# DatatrakEPROMEmu.net
KiCad netlist of a schematic drawn in EAGLE
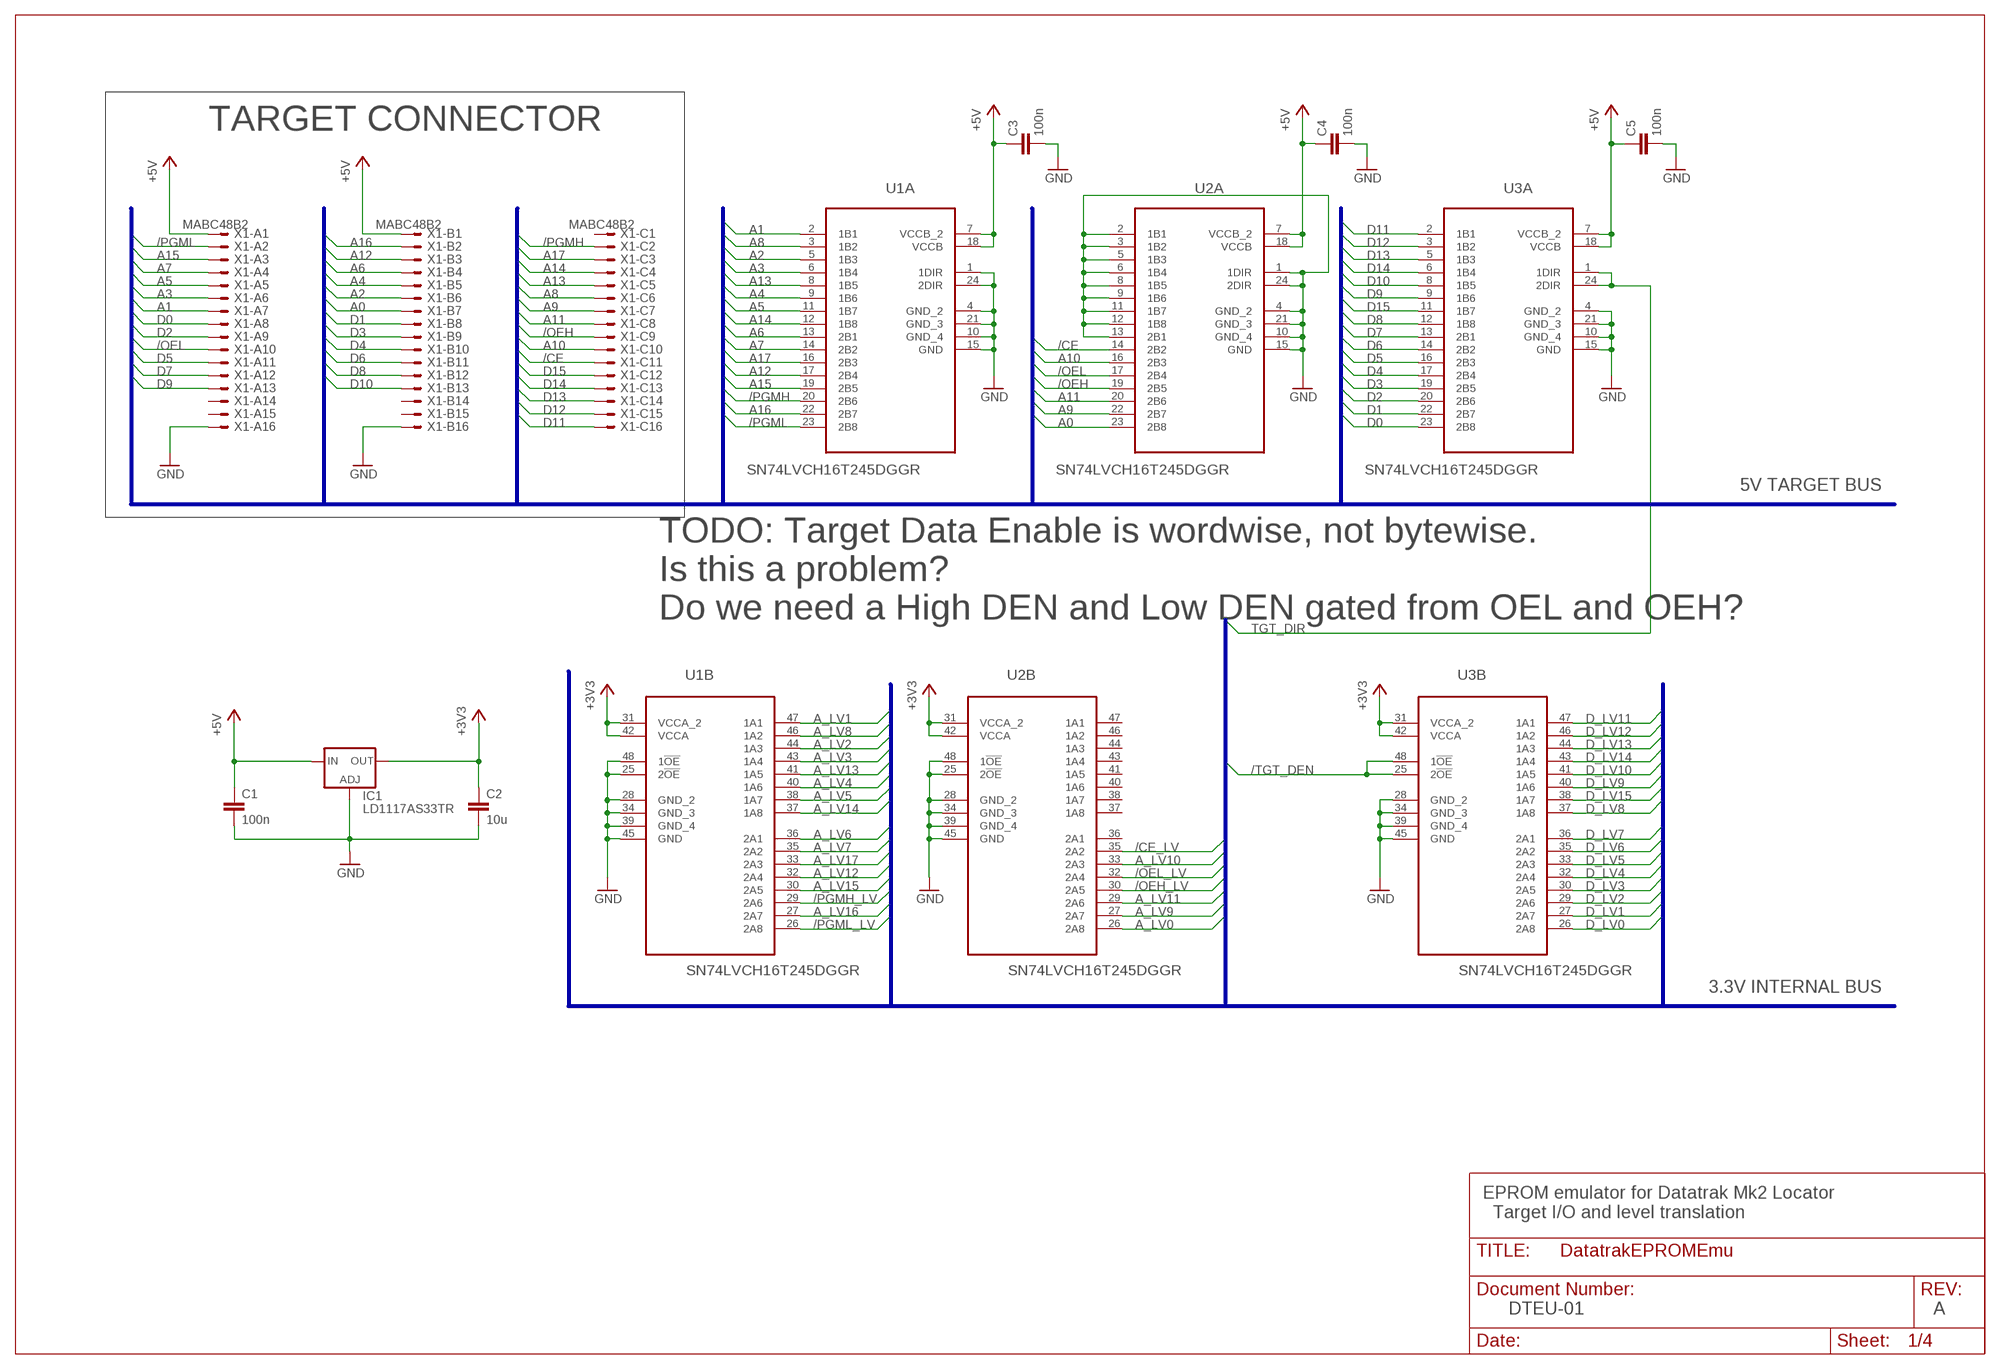
[diagram p0: schematic, sheet 1]
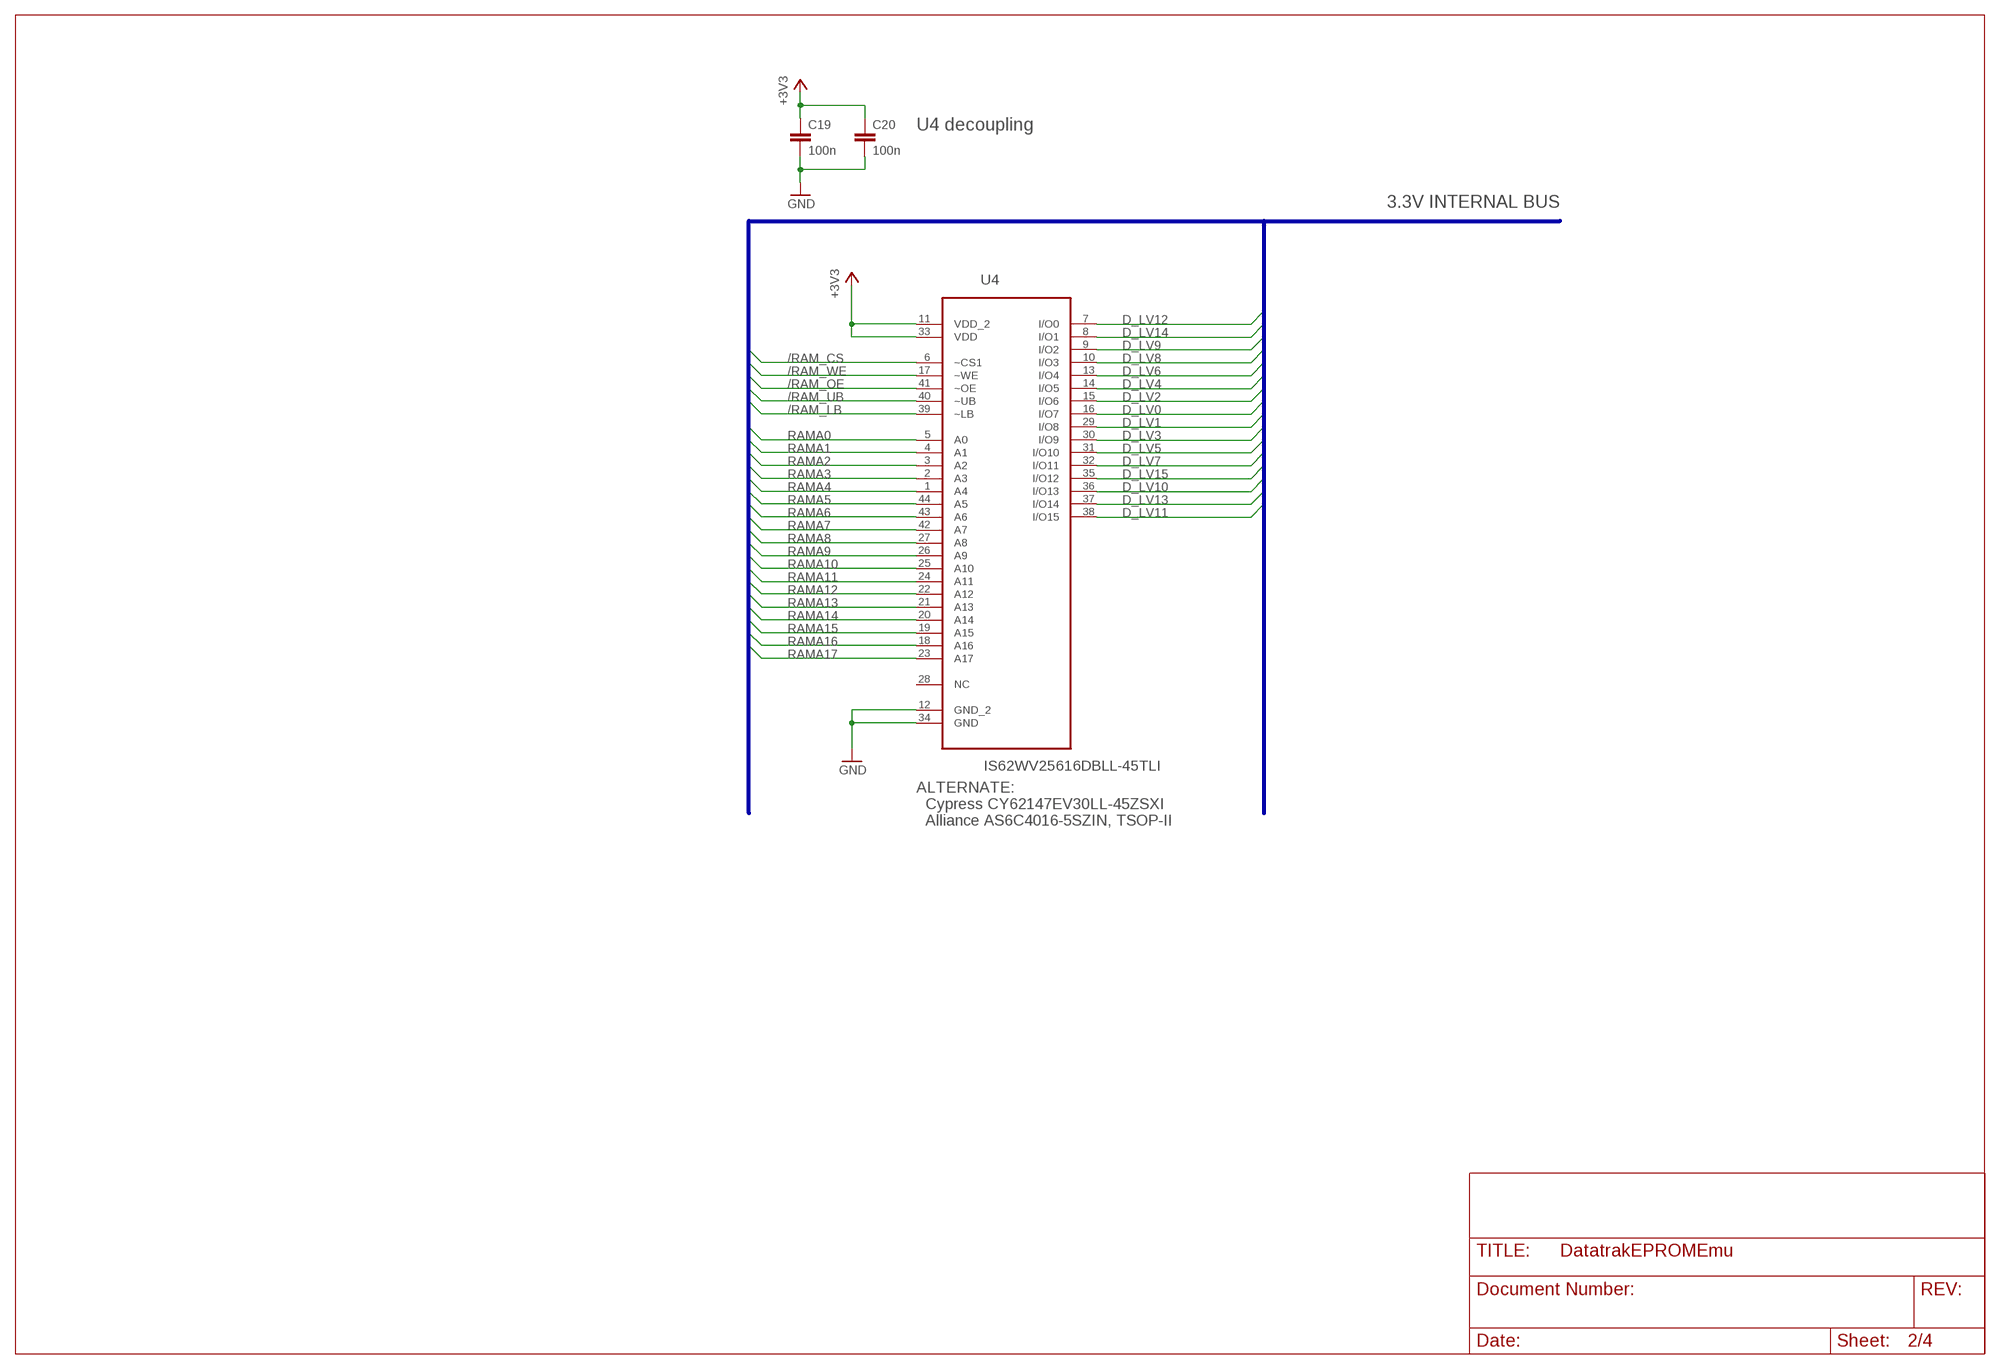
[diagram p1: schematic, sheet 2]
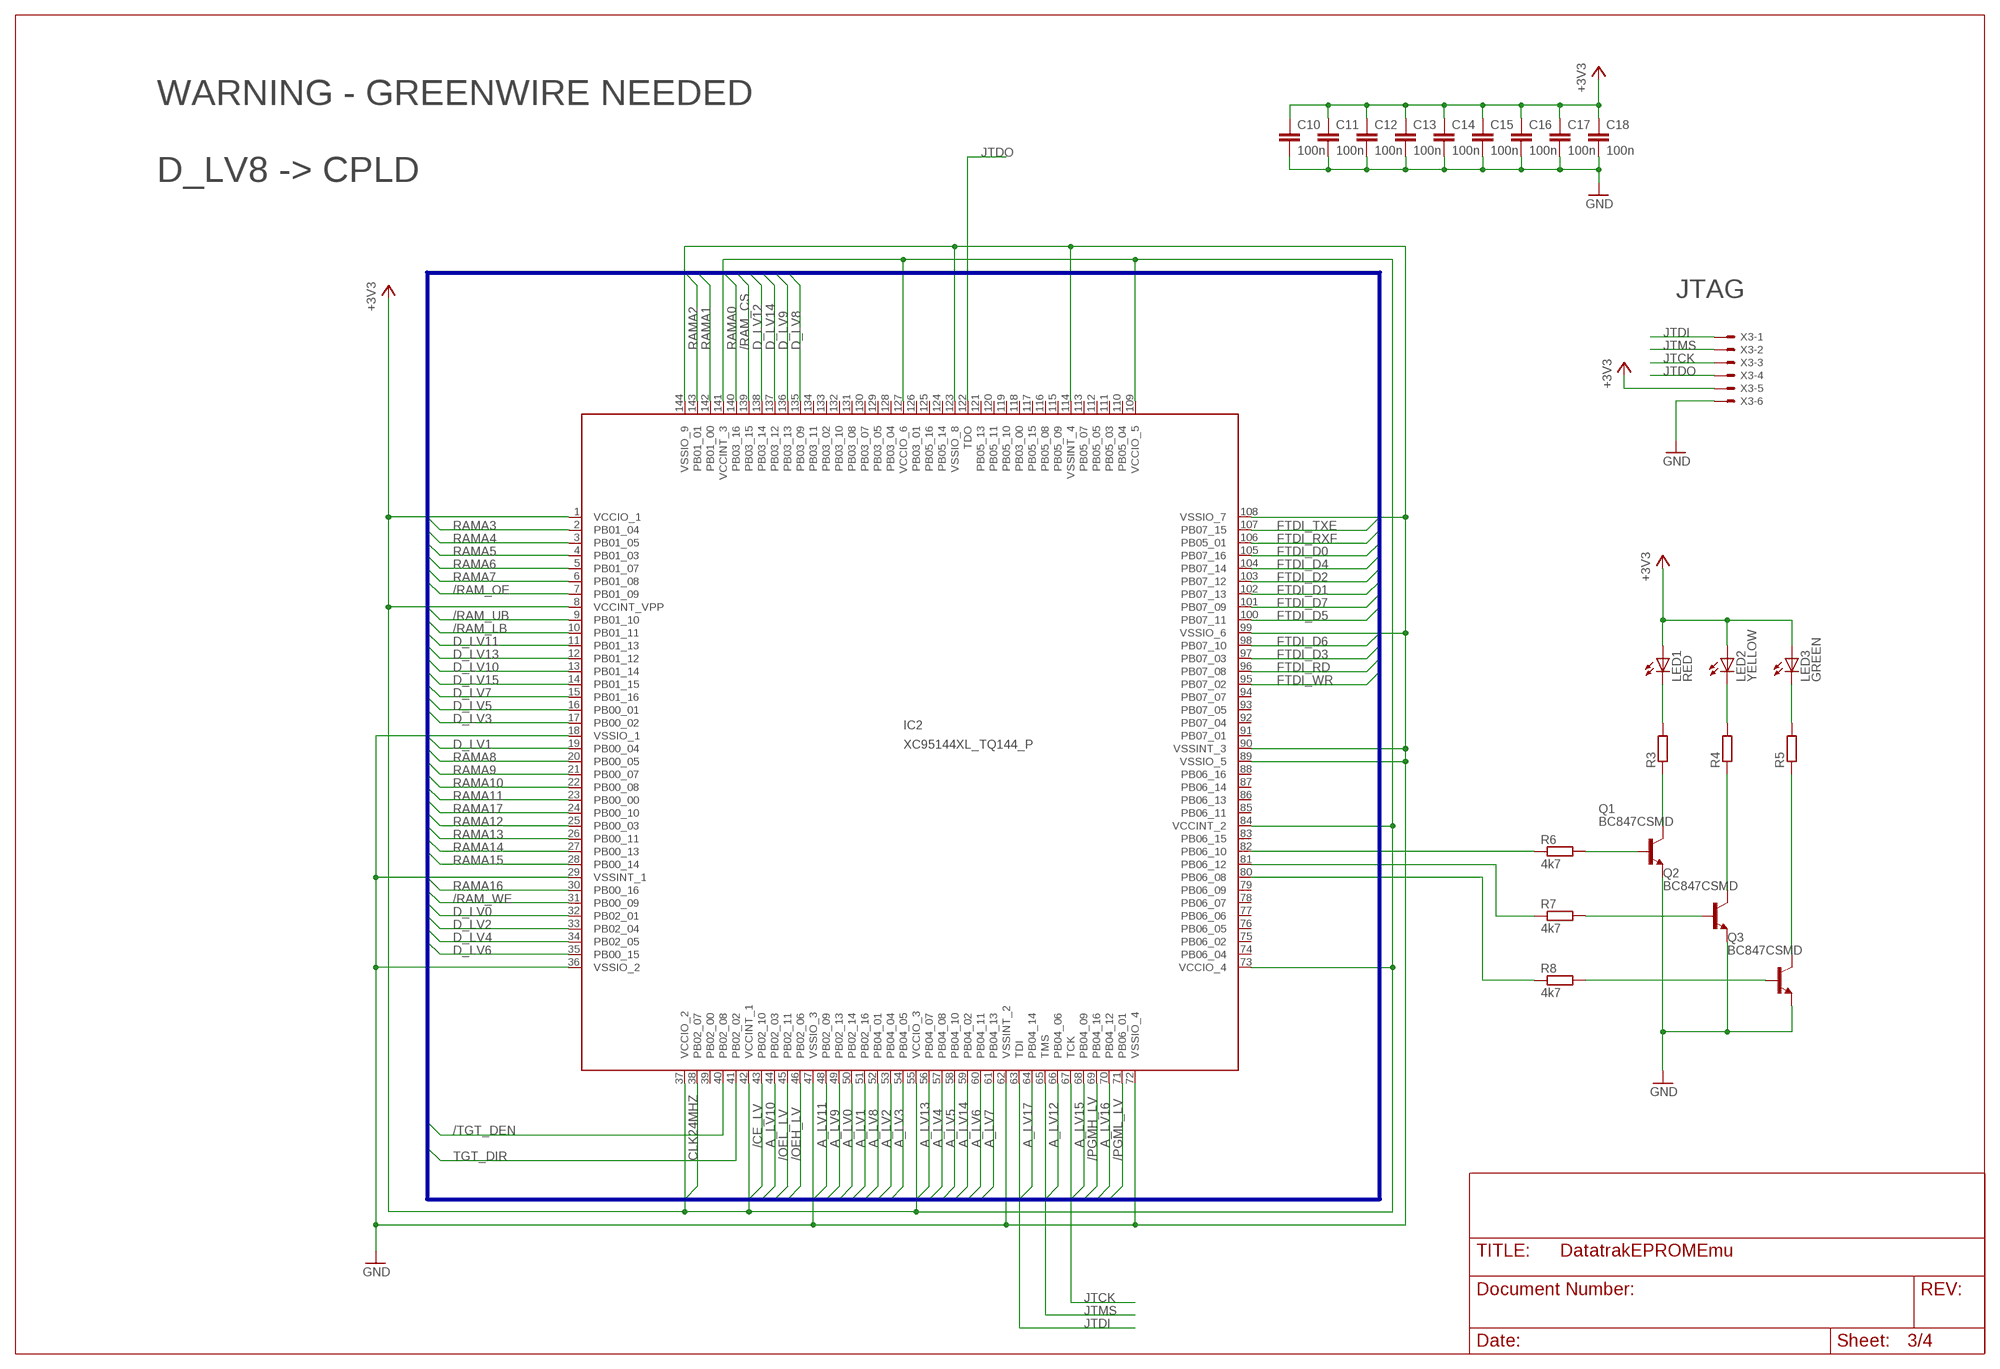
[diagram p2: schematic, sheet 3]
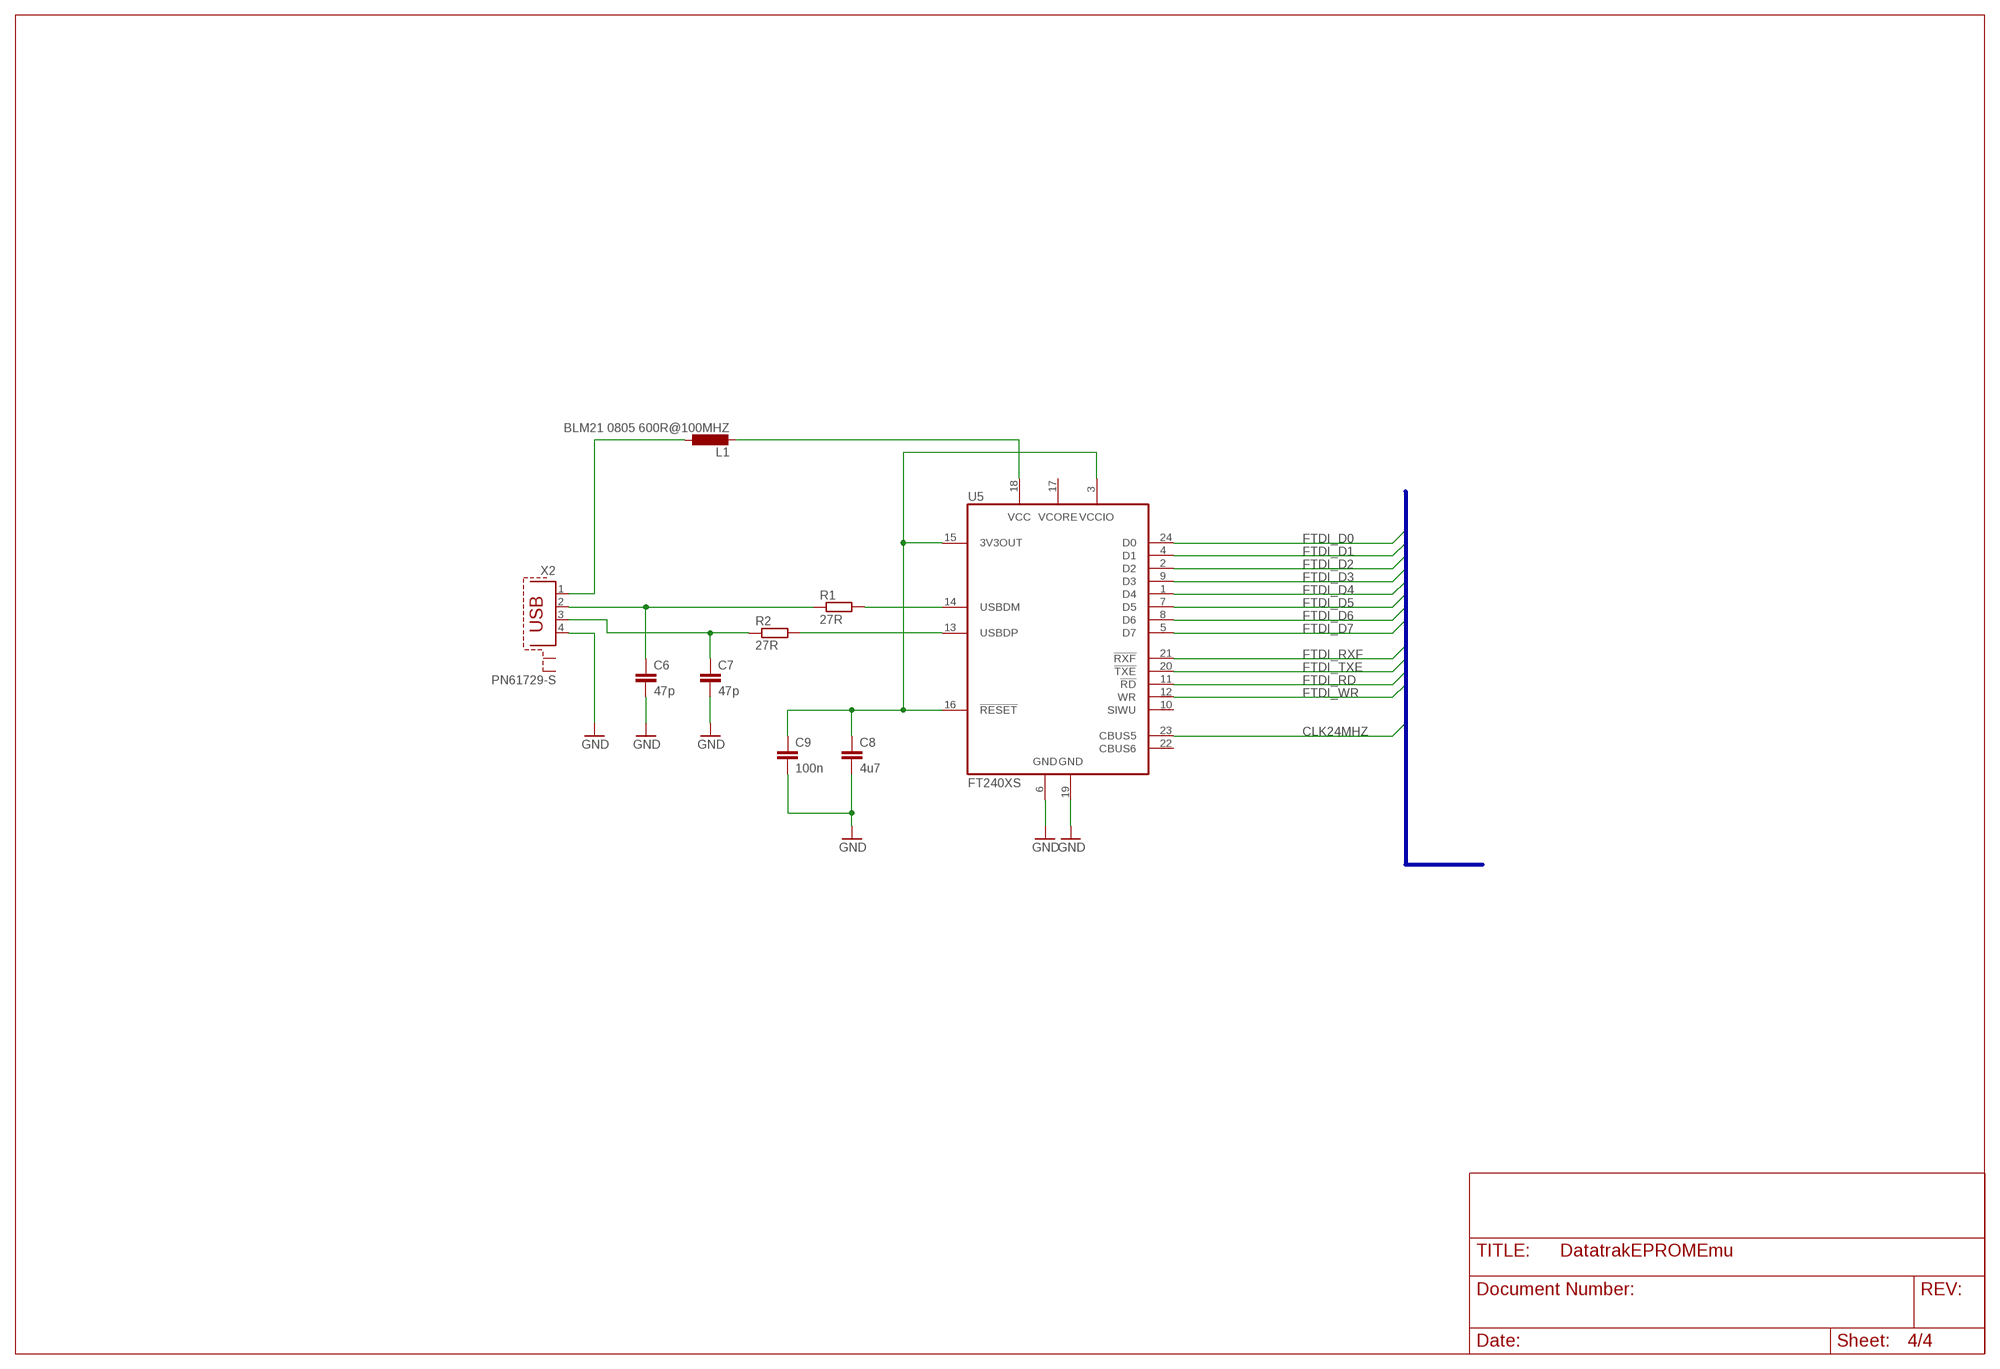
[diagram p3: schematic, sheet 4]

(export (version "E")
  (design (tool "Eeschema 10.0.6"))
  (components
    (comp (ref "C19")
      (value "100n")
      (footprint "eagle-import:C0805")
      (libsource (lib "eagle-import") (part "C-EUC0805"))
    )
    (comp (ref "C20")
      (value "100n")
      (footprint "eagle-import:C0805")
      (libsource (lib "eagle-import") (part "C-EUC0805"))
    )
    (comp (ref "U4")
      (value "IS62WV25616DBLL-45TLI")
      (footprint "eagle-import:SOP80P1176X120-44N")
      (libsource (lib "eagle-import") (part "IS62WV25616DBLL-45TLI"))
    )
    (comp (ref "C1")
      (value "100n")
      (footprint "eagle-import:C0805")
      (libsource (lib "eagle-import") (part "C-EUC0805"))
    )
    (comp (ref "C2")
      (value "10u")
      (footprint "eagle-import:C0805")
      (libsource (lib "eagle-import") (part "C-EUC0805"))
    )
    (comp (ref "C3")
      (value "100n")
      (footprint "eagle-import:C0805")
      (libsource (lib "eagle-import") (part "C-EUC0805"))
    )
    (comp (ref "C4")
      (value "100n")
      (footprint "eagle-import:C0805")
      (libsource (lib "eagle-import") (part "C-EUC0805"))
    )
    (comp (ref "C5")
      (value "100n")
      (footprint "eagle-import:C0805")
      (libsource (lib "eagle-import") (part "C-EUC0805"))
    )
    (comp (ref "IC1")
      (value "LD1117AS33TR")
      (footprint "eagle-import:SOT223")
      (libsource (lib "eagle-import") (part "LD117A?S33TR"))
    )
    (comp (ref "U1")
      (value "SN74LVCH16T245DGGR")
      (footprint "eagle-import:SOP50P810X120-48N")
      (libsource (lib "eagle-import") (part "SN74LVCH16T245DGGR"))
    )
    (comp (ref "U2")
      (value "SN74LVCH16T245DGGR")
      (footprint "eagle-import:SOP50P810X120-48N")
      (libsource (lib "eagle-import") (part "SN74LVCH16T245DGGR"))
    )
    (comp (ref "U3")
      (value "SN74LVCH16T245DGGR")
      (footprint "eagle-import:SOP50P810X120-48N")
      (libsource (lib "eagle-import") (part "SN74LVCH16T245DGGR"))
    )
    (comp (ref "X1")
      (value "MABC48B2")
      (footprint "eagle-import:MABC48B2")
      (libsource (lib "eagle-import") (part "MABC48B2"))
    )
    (comp (ref "C6")
      (value "47p")
      (footprint "eagle-import:C0805")
      (libsource (lib "eagle-import") (part "C-EUC0805"))
    )
    (comp (ref "C7")
      (value "47p")
      (footprint "eagle-import:C0805")
      (libsource (lib "eagle-import") (part "C-EUC0805"))
    )
    (comp (ref "C8")
      (value "4u7")
      (footprint "eagle-import:C0805")
      (libsource (lib "eagle-import") (part "C-EUC0805"))
    )
    (comp (ref "C9")
      (value "100n")
      (footprint "eagle-import:C0805")
      (libsource (lib "eagle-import") (part "C-EUC0805"))
    )
    (comp (ref "L1")
      (value "BLM21 0805 600R@100MHZ")
      (footprint "eagle-import:L2012C")
      (libsource (lib "eagle-import") (part "L-EUL2012C"))
    )
    (comp (ref "R1")
      (value "27R")
      (footprint "eagle-import:R0805")
      (libsource (lib "eagle-import") (part "R-EU_R0805"))
    )
    (comp (ref "R2")
      (value "27R")
      (footprint "eagle-import:R0805")
      (libsource (lib "eagle-import") (part "R-EU_R0805"))
    )
    (comp (ref "U5")
      (value "FT240XS")
      (footprint "eagle-import:SSOP24")
      (libsource (lib "eagle-import") (part "FT240XS"))
    )
    (comp (ref "X2")
      (value "PN61729-S")
      (footprint "eagle-import:PN61729-S")
      (libsource (lib "eagle-import") (part "PN61729-S"))
    )
    (comp (ref "C10")
      (value "100n")
      (footprint "eagle-import:C0805")
      (libsource (lib "eagle-import") (part "C-EUC0805"))
    )
    (comp (ref "C11")
      (value "100n")
      (footprint "eagle-import:C0805")
      (libsource (lib "eagle-import") (part "C-EUC0805"))
    )
    (comp (ref "C12")
      (value "100n")
      (footprint "eagle-import:C0805")
      (libsource (lib "eagle-import") (part "C-EUC0805"))
    )
    (comp (ref "C13")
      (value "100n")
      (footprint "eagle-import:C0805")
      (libsource (lib "eagle-import") (part "C-EUC0805"))
    )
    (comp (ref "C14")
      (value "100n")
      (footprint "eagle-import:C0805")
      (libsource (lib "eagle-import") (part "C-EUC0805"))
    )
    (comp (ref "C15")
      (value "100n")
      (footprint "eagle-import:C0805")
      (libsource (lib "eagle-import") (part "C-EUC0805"))
    )
    (comp (ref "C16")
      (value "100n")
      (footprint "eagle-import:C0805")
      (libsource (lib "eagle-import") (part "C-EUC0805"))
    )
    (comp (ref "C17")
      (value "100n")
      (footprint "eagle-import:C0805")
      (libsource (lib "eagle-import") (part "C-EUC0805"))
    )
    (comp (ref "C18")
      (value "100n")
      (footprint "eagle-import:C0805")
      (libsource (lib "eagle-import") (part "C-EUC0805"))
    )
    (comp (ref "IC2")
      (value "XC95144XL_TQ144_P")
      (footprint "eagle-import:TQ144")
      (libsource (lib "eagle-import") (part "XC95144XL_TQ144_P"))
    )
    (comp (ref "LED1")
      (value "RED")
      (footprint "eagle-import:SML0805")
      (libsource (lib "eagle-import") (part "LEDSML0805"))
    )
    (comp (ref "LED2")
      (value "YELLOW")
      (footprint "eagle-import:SML0805")
      (libsource (lib "eagle-import") (part "LEDSML0805"))
    )
    (comp (ref "LED3")
      (value "GREEN")
      (footprint "eagle-import:SML0805")
      (libsource (lib "eagle-import") (part "LEDSML0805"))
    )
    (comp (ref "Q1")
      (value "BC847CSMD")
      (footprint "eagle-import:SOT23")
      (libsource (lib "eagle-import") (part "BC847SMDC"))
    )
    (comp (ref "Q2")
      (value "BC847CSMD")
      (footprint "eagle-import:SOT23")
      (libsource (lib "eagle-import") (part "BC847SMDC"))
    )
    (comp (ref "Q3")
      (value "BC847CSMD")
      (footprint "eagle-import:SOT23")
      (libsource (lib "eagle-import") (part "BC847SMDC"))
    )
    (comp (ref "R3")
      (value "R-EU_R0805")
      (footprint "eagle-import:R0805")
      (libsource (lib "eagle-import") (part "R-EU_R0805"))
    )
    (comp (ref "R4")
      (value "R-EU_R0805")
      (footprint "eagle-import:R0805")
      (libsource (lib "eagle-import") (part "R-EU_R0805"))
    )
    (comp (ref "R5")
      (value "R-EU_R0805")
      (footprint "eagle-import:R0805")
      (libsource (lib "eagle-import") (part "R-EU_R0805"))
    )
    (comp (ref "R6")
      (value "4k7")
      (footprint "eagle-import:R0805")
      (libsource (lib "eagle-import") (part "R-EU_R0805"))
    )
    (comp (ref "R7")
      (value "4k7")
      (footprint "eagle-import:R0805")
      (libsource (lib "eagle-import") (part "R-EU_R0805"))
    )
    (comp (ref "R8")
      (value "4k7")
      (footprint "eagle-import:R0805")
      (libsource (lib "eagle-import") (part "R-EU_R0805"))
    )
    (comp (ref "X3")
      (value "22-23-2061")
      (footprint "eagle-import:22-23-2061")
      (fields (field (name "MF") "MOLEX"))
      (libsource (lib "eagle-import") (part "22-23-2061"))
    )
  )
  (nets
    (net (code "1") (name "+3V3") (class "Default")
      (node (ref "C10") (pin "1") (pinfunction "1_1") (pintype "passive"))
      (node (ref "C11") (pin "1") (pinfunction "1_1") (pintype "passive"))
      (node (ref "C12") (pin "1") (pinfunction "1_1") (pintype "passive"))
      (node (ref "C13") (pin "1") (pinfunction "1_1") (pintype "passive"))
      (node (ref "C14") (pin "1") (pinfunction "1_1") (pintype "passive"))
      (node (ref "C15") (pin "1") (pinfunction "1_1") (pintype "passive"))
      (node (ref "C16") (pin "1") (pinfunction "1_1") (pintype "passive"))
      (node (ref "C17") (pin "1") (pinfunction "1_1") (pintype "passive"))
      (node (ref "C18") (pin "1") (pinfunction "1_1") (pintype "passive"))
      (node (ref "C19") (pin "1") (pinfunction "1_1") (pintype "passive"))
      (node (ref "C2") (pin "1") (pinfunction "1_1") (pintype "passive"))
      (node (ref "C20") (pin "1") (pinfunction "1_1") (pintype "passive"))
      (node (ref "IC1") (pin "4") (pinfunction "OUT_4") (pintype "passive"))
      (node (ref "IC2") (pin "1") (pinfunction "VCCIO_1_1") (pintype "passive"))
      (node (ref "IC2") (pin "109") (pinfunction "VCCIO_5_109") (pintype "passive"))
      (node (ref "IC2") (pin "127") (pinfunction "VCCIO_6_127") (pintype "passive"))
      (node (ref "IC2") (pin "141") (pinfunction "VCCINT_3_141") (pintype "passive"))
      (node (ref "IC2") (pin "37") (pinfunction "VCCIO_2_37") (pintype "passive"))
      (node (ref "IC2") (pin "42") (pinfunction "VCCINT_1_42") (pintype "passive"))
      (node (ref "IC2") (pin "55") (pinfunction "VCCIO_3_55") (pintype "passive"))
      (node (ref "IC2") (pin "73") (pinfunction "VCCIO_4_73") (pintype "passive"))
      (node (ref "IC2") (pin "8") (pinfunction "VCCINT_VPP_8") (pintype "passive"))
      (node (ref "IC2") (pin "84") (pinfunction "VCCINT_2_84") (pintype "passive"))
      (node (ref "LED1") (pin "A") (pinfunction "A_A") (pintype "passive"))
      (node (ref "LED2") (pin "A") (pinfunction "A_A") (pintype "passive"))
      (node (ref "LED3") (pin "A") (pinfunction "A_A") (pintype "passive"))
      (node (ref "U1") (pin "31") (pinfunction "VCCA_2_31") (pintype "power_in"))
      (node (ref "U1") (pin "42") (pinfunction "VCCA_42") (pintype "power_in"))
      (node (ref "U2") (pin "31") (pinfunction "VCCA_2_31") (pintype "power_in"))
      (node (ref "U2") (pin "42") (pinfunction "VCCA_42") (pintype "power_in"))
      (node (ref "U3") (pin "31") (pinfunction "VCCA_2_31") (pintype "power_in"))
      (node (ref "U3") (pin "42") (pinfunction "VCCA_42") (pintype "power_in"))
      (node (ref "U4") (pin "11") (pinfunction "VDD_2_11") (pintype "power_in"))
      (node (ref "U4") (pin "33") (pinfunction "VDD_33") (pintype "power_in"))
      (node (ref "X3") (pin "5") (pinfunction "S_5") (pintype "passive"))
    )
    (net (code "2") (name "+5V") (class "Default")
      (node (ref "C1") (pin "1") (pinfunction "1_1") (pintype "passive"))
      (node (ref "C3") (pin "1") (pinfunction "1_1") (pintype "passive"))
      (node (ref "C4") (pin "1") (pinfunction "1_1") (pintype "passive"))
      (node (ref "C5") (pin "1") (pinfunction "1_1") (pintype "passive"))
      (node (ref "IC1") (pin "3") (pinfunction "IN_3") (pintype "input"))
      (node (ref "U1") (pin "18") (pinfunction "VCCB_18") (pintype "power_in"))
      (node (ref "U1") (pin "7") (pinfunction "VCCB_2_7") (pintype "power_in"))
      (node (ref "U2") (pin "18") (pinfunction "VCCB_18") (pintype "power_in"))
      (node (ref "U2") (pin "7") (pinfunction "VCCB_2_7") (pintype "power_in"))
      (node (ref "U3") (pin "18") (pinfunction "VCCB_18") (pintype "power_in"))
      (node (ref "U3") (pin "7") (pinfunction "VCCB_2_7") (pintype "power_in"))
      (node (ref "X1") (pin "A1") (pinfunction "S_A1") (pintype "passive"))
      (node (ref "X1") (pin "B1") (pinfunction "S_B1") (pintype "passive"))
    )
    (net (code "3") (name "A0") (class "Default")
      (node (ref "U2") (pin "23") (pinfunction "2B8_23") (pintype "output"))
      (node (ref "X1") (pin "B7") (pinfunction "S_B7") (pintype "passive"))
    )
    (net (code "4") (name "A1") (class "Default")
      (node (ref "U1") (pin "2") (pinfunction "1B1_2") (pintype "output"))
      (node (ref "X1") (pin "A7") (pinfunction "S_A7") (pintype "passive"))
    )
    (net (code "5") (name "A2") (class "Default")
      (node (ref "U1") (pin "5") (pinfunction "1B3_5") (pintype "output"))
      (node (ref "X1") (pin "B6") (pinfunction "S_B6") (pintype "passive"))
    )
    (net (code "6") (name "A3") (class "Default")
      (node (ref "U1") (pin "6") (pinfunction "1B4_6") (pintype "output"))
      (node (ref "X1") (pin "A6") (pinfunction "S_A6") (pintype "passive"))
    )
    (net (code "7") (name "A4") (class "Default")
      (node (ref "U1") (pin "9") (pinfunction "1B6_9") (pintype "output"))
      (node (ref "X1") (pin "B5") (pinfunction "S_B5") (pintype "passive"))
    )
    (net (code "8") (name "A5") (class "Default")
      (node (ref "U1") (pin "11") (pinfunction "1B7_11") (pintype "output"))
      (node (ref "X1") (pin "A5") (pinfunction "S_A5") (pintype "passive"))
    )
    (net (code "9") (name "A6") (class "Default")
      (node (ref "U1") (pin "13") (pinfunction "2B1_13") (pintype "output"))
      (node (ref "X1") (pin "B4") (pinfunction "S_B4") (pintype "passive"))
    )
    (net (code "10") (name "A7") (class "Default")
      (node (ref "U1") (pin "14") (pinfunction "2B2_14") (pintype "output"))
      (node (ref "X1") (pin "A4") (pinfunction "S_A4") (pintype "passive"))
    )
    (net (code "11") (name "A8") (class "Default")
      (node (ref "U1") (pin "3") (pinfunction "1B2_3") (pintype "output"))
      (node (ref "X1") (pin "C6") (pinfunction "S_C6") (pintype "passive"))
    )
    (net (code "12") (name "A9") (class "Default")
      (node (ref "U2") (pin "22") (pinfunction "2B7_22") (pintype "output"))
      (node (ref "X1") (pin "C7") (pinfunction "S_C7") (pintype "passive"))
    )
    (net (code "13") (name "A10") (class "Default")
      (node (ref "U2") (pin "16") (pinfunction "2B3_16") (pintype "output"))
      (node (ref "X1") (pin "C10") (pinfunction "S_C10") (pintype "passive"))
    )
    (net (code "14") (name "A11") (class "Default")
      (node (ref "U2") (pin "20") (pinfunction "2B6_20") (pintype "output"))
      (node (ref "X1") (pin "C8") (pinfunction "S_C8") (pintype "passive"))
    )
    (net (code "15") (name "A12") (class "Default")
      (node (ref "U1") (pin "17") (pinfunction "2B4_17") (pintype "output"))
      (node (ref "X1") (pin "B3") (pinfunction "S_B3") (pintype "passive"))
    )
    (net (code "16") (name "A13") (class "Default")
      (node (ref "U1") (pin "8") (pinfunction "1B5_8") (pintype "output"))
      (node (ref "X1") (pin "C5") (pinfunction "S_C5") (pintype "passive"))
    )
    (net (code "17") (name "A14") (class "Default")
      (node (ref "U1") (pin "12") (pinfunction "1B8_12") (pintype "output"))
      (node (ref "X1") (pin "C4") (pinfunction "S_C4") (pintype "passive"))
    )
    (net (code "18") (name "A15") (class "Default")
      (node (ref "U1") (pin "19") (pinfunction "2B5_19") (pintype "output"))
      (node (ref "X1") (pin "A3") (pinfunction "S_A3") (pintype "passive"))
    )
    (net (code "19") (name "A16") (class "Default")
      (node (ref "U1") (pin "22") (pinfunction "2B7_22") (pintype "output"))
      (node (ref "X1") (pin "B2") (pinfunction "S_B2") (pintype "passive"))
    )
    (net (code "20") (name "A17") (class "Default")
      (node (ref "U1") (pin "16") (pinfunction "2B3_16") (pintype "output"))
      (node (ref "X1") (pin "C3") (pinfunction "S_C3") (pintype "passive"))
    )
    (net (code "21") (name "A_LV0") (class "Default")
      (node (ref "IC2") (pin "50") (pinfunction "PB02_14_50") (pintype "bidirectional"))
      (node (ref "U2") (pin "26") (pinfunction "2A8_26") (pintype "output"))
    )
    (net (code "22") (name "A_LV1") (class "Default")
      (node (ref "IC2") (pin "51") (pinfunction "PB02_16_51") (pintype "bidirectional"))
      (node (ref "U1") (pin "47") (pinfunction "1A1_47") (pintype "output"))
    )
    (net (code "23") (name "A_LV2") (class "Default")
      (node (ref "IC2") (pin "53") (pinfunction "PB04_04_53") (pintype "bidirectional"))
      (node (ref "U1") (pin "44") (pinfunction "1A3_44") (pintype "output"))
    )
    (net (code "24") (name "A_LV3") (class "Default")
      (node (ref "IC2") (pin "54") (pinfunction "PB04_05_54") (pintype "bidirectional"))
      (node (ref "U1") (pin "43") (pinfunction "1A4_43") (pintype "output"))
    )
    (net (code "25") (name "A_LV4") (class "Default")
      (node (ref "IC2") (pin "57") (pinfunction "PB04_08_57") (pintype "bidirectional"))
      (node (ref "U1") (pin "40") (pinfunction "1A6_40") (pintype "output"))
    )
    (net (code "26") (name "A_LV5") (class "Default")
      (node (ref "IC2") (pin "58") (pinfunction "PB04_10_58") (pintype "bidirectional"))
      (node (ref "U1") (pin "38") (pinfunction "1A7_38") (pintype "output"))
    )
    (net (code "27") (name "A_LV6") (class "Default")
      (node (ref "IC2") (pin "60") (pinfunction "PB04_11_60") (pintype "bidirectional"))
      (node (ref "U1") (pin "36") (pinfunction "2A1_36") (pintype "output"))
    )
    (net (code "28") (name "A_LV7") (class "Default")
      (node (ref "IC2") (pin "61") (pinfunction "PB04_13_61") (pintype "bidirectional"))
      (node (ref "U1") (pin "35") (pinfunction "2A2_35") (pintype "output"))
    )
    (net (code "29") (name "A_LV8") (class "Default")
      (node (ref "IC2") (pin "52") (pinfunction "PB04_01_52") (pintype "bidirectional"))
      (node (ref "U1") (pin "46") (pinfunction "1A2_46") (pintype "output"))
    )
    (net (code "30") (name "A_LV9") (class "Default")
      (node (ref "IC2") (pin "49") (pinfunction "PB02_13_49") (pintype "bidirectional"))
      (node (ref "U2") (pin "27") (pinfunction "2A7_27") (pintype "output"))
    )
    (net (code "31") (name "A_LV10") (class "Default")
      (node (ref "IC2") (pin "44") (pinfunction "PB02_03_44") (pintype "bidirectional"))
      (node (ref "U2") (pin "33") (pinfunction "2A3_33") (pintype "output"))
    )
    (net (code "32") (name "A_LV11") (class "Default")
      (node (ref "IC2") (pin "48") (pinfunction "PB02_09_48") (pintype "bidirectional"))
      (node (ref "U2") (pin "29") (pinfunction "2A6_29") (pintype "output"))
    )
    (net (code "33") (name "A_LV12") (class "Default")
      (node (ref "IC2") (pin "66") (pinfunction "PB04_06_66") (pintype "bidirectional"))
      (node (ref "U1") (pin "32") (pinfunction "2A4_32") (pintype "output"))
    )
    (net (code "34") (name "A_LV13") (class "Default")
      (node (ref "IC2") (pin "56") (pinfunction "PB04_07_56") (pintype "bidirectional"))
      (node (ref "U1") (pin "41") (pinfunction "1A5_41") (pintype "output"))
    )
    (net (code "35") (name "A_LV14") (class "Default")
      (node (ref "IC2") (pin "59") (pinfunction "PB04_02_59") (pintype "bidirectional"))
      (node (ref "U1") (pin "37") (pinfunction "1A8_37") (pintype "output"))
    )
    (net (code "36") (name "A_LV15") (class "Default")
      (node (ref "IC2") (pin "68") (pinfunction "PB04_09_68") (pintype "bidirectional"))
      (node (ref "U1") (pin "30") (pinfunction "2A5_30") (pintype "output"))
    )
    (net (code "37") (name "A_LV16") (class "Default")
      (node (ref "IC2") (pin "70") (pinfunction "PB04_12_70") (pintype "bidirectional"))
      (node (ref "U1") (pin "27") (pinfunction "2A7_27") (pintype "output"))
    )
    (net (code "38") (name "A_LV17") (class "Default")
      (node (ref "IC2") (pin "64") (pinfunction "PB04_14_64") (pintype "bidirectional"))
      (node (ref "U1") (pin "33") (pinfunction "2A3_33") (pintype "output"))
    )
    (net (code "39") (name "CLK24MHZ") (class "Default")
      (node (ref "IC2") (pin "38") (pinfunction "PB02_07_38") (pintype "bidirectional"))
      (node (ref "U5") (pin "23") (pinfunction "CBUS5_23") (pintype "bidirectional"))
    )
    (net (code "40") (name "D0") (class "Default")
      (node (ref "U3") (pin "23") (pinfunction "2B8_23") (pintype "output"))
      (node (ref "X1") (pin "A8") (pinfunction "S_A8") (pintype "passive"))
    )
    (net (code "41") (name "D1") (class "Default")
      (node (ref "U3") (pin "22") (pinfunction "2B7_22") (pintype "output"))
      (node (ref "X1") (pin "B8") (pinfunction "S_B8") (pintype "passive"))
    )
    (net (code "42") (name "D2") (class "Default")
      (node (ref "U3") (pin "20") (pinfunction "2B6_20") (pintype "output"))
      (node (ref "X1") (pin "A9") (pinfunction "S_A9") (pintype "passive"))
    )
    (net (code "43") (name "D3") (class "Default")
      (node (ref "U3") (pin "19") (pinfunction "2B5_19") (pintype "output"))
      (node (ref "X1") (pin "B9") (pinfunction "S_B9") (pintype "passive"))
    )
    (net (code "44") (name "D4") (class "Default")
      (node (ref "U3") (pin "17") (pinfunction "2B4_17") (pintype "output"))
      (node (ref "X1") (pin "B10") (pinfunction "S_B10") (pintype "passive"))
    )
    (net (code "45") (name "D5") (class "Default")
      (node (ref "U3") (pin "16") (pinfunction "2B3_16") (pintype "output"))
      (node (ref "X1") (pin "A11") (pinfunction "S_A11") (pintype "passive"))
    )
    (net (code "46") (name "D6") (class "Default")
      (node (ref "U3") (pin "14") (pinfunction "2B2_14") (pintype "output"))
      (node (ref "X1") (pin "B11") (pinfunction "S_B11") (pintype "passive"))
    )
    (net (code "47") (name "D7") (class "Default")
      (node (ref "U3") (pin "13") (pinfunction "2B1_13") (pintype "output"))
      (node (ref "X1") (pin "A12") (pinfunction "S_A12") (pintype "passive"))
    )
    (net (code "48") (name "D8") (class "Default")
      (node (ref "U3") (pin "12") (pinfunction "1B8_12") (pintype "output"))
      (node (ref "X1") (pin "B12") (pinfunction "S_B12") (pintype "passive"))
    )
    (net (code "49") (name "D9") (class "Default")
      (node (ref "U3") (pin "9") (pinfunction "1B6_9") (pintype "output"))
      (node (ref "X1") (pin "A13") (pinfunction "S_A13") (pintype "passive"))
    )
    (net (code "50") (name "D10") (class "Default")
      (node (ref "U3") (pin "8") (pinfunction "1B5_8") (pintype "output"))
      (node (ref "X1") (pin "B13") (pinfunction "S_B13") (pintype "passive"))
    )
    (net (code "51") (name "D11") (class "Default")
      (node (ref "U3") (pin "2") (pinfunction "1B1_2") (pintype "output"))
      (node (ref "X1") (pin "C16") (pinfunction "S_C16") (pintype "passive"))
    )
    (net (code "52") (name "D12") (class "Default")
      (node (ref "U3") (pin "3") (pinfunction "1B2_3") (pintype "output"))
      (node (ref "X1") (pin "C15") (pinfunction "S_C15") (pintype "passive"))
    )
    (net (code "53") (name "D13") (class "Default")
      (node (ref "U3") (pin "5") (pinfunction "1B3_5") (pintype "output"))
      (node (ref "X1") (pin "C14") (pinfunction "S_C14") (pintype "passive"))
    )
    (net (code "54") (name "D14") (class "Default")
      (node (ref "U3") (pin "6") (pinfunction "1B4_6") (pintype "output"))
      (node (ref "X1") (pin "C13") (pinfunction "S_C13") (pintype "passive"))
    )
    (net (code "55") (name "D15") (class "Default")
      (node (ref "U3") (pin "11") (pinfunction "1B7_11") (pintype "output"))
      (node (ref "X1") (pin "C12") (pinfunction "S_C12") (pintype "passive"))
    )
    (net (code "56") (name "D_LV0") (class "Default")
      (node (ref "IC2") (pin "32") (pinfunction "PB02_01_32") (pintype "bidirectional"))
      (node (ref "U3") (pin "26") (pinfunction "2A8_26") (pintype "output"))
      (node (ref "U4") (pin "16") (pinfunction "I/O7_16") (pintype "bidirectional"))
    )
    (net (code "57") (name "D_LV1") (class "Default")
      (node (ref "IC2") (pin "19") (pinfunction "PB00_04_19") (pintype "bidirectional"))
      (node (ref "U3") (pin "27") (pinfunction "2A7_27") (pintype "output"))
      (node (ref "U4") (pin "29") (pinfunction "I/O8_29") (pintype "bidirectional"))
    )
    (net (code "58") (name "D_LV2") (class "Default")
      (node (ref "IC2") (pin "33") (pinfunction "PB02_04_33") (pintype "bidirectional"))
      (node (ref "U3") (pin "29") (pinfunction "2A6_29") (pintype "output"))
      (node (ref "U4") (pin "15") (pinfunction "I/O6_15") (pintype "bidirectional"))
    )
    (net (code "59") (name "D_LV3") (class "Default")
      (node (ref "IC2") (pin "17") (pinfunction "PB00_02_17") (pintype "bidirectional"))
      (node (ref "U3") (pin "30") (pinfunction "2A5_30") (pintype "output"))
      (node (ref "U4") (pin "30") (pinfunction "I/O9_30") (pintype "bidirectional"))
    )
    (net (code "60") (name "D_LV4") (class "Default")
      (node (ref "IC2") (pin "34") (pinfunction "PB02_05_34") (pintype "bidirectional"))
      (node (ref "U3") (pin "32") (pinfunction "2A4_32") (pintype "output"))
      (node (ref "U4") (pin "14") (pinfunction "I/O5_14") (pintype "bidirectional"))
    )
    (net (code "61") (name "D_LV5") (class "Default")
      (node (ref "IC2") (pin "16") (pinfunction "PB00_01_16") (pintype "bidirectional"))
      (node (ref "U3") (pin "33") (pinfunction "2A3_33") (pintype "output"))
      (node (ref "U4") (pin "31") (pinfunction "I/O10_31") (pintype "bidirectional"))
    )
    (net (code "62") (name "D_LV6") (class "Default")
      (node (ref "IC2") (pin "35") (pinfunction "PB00_15_35") (pintype "bidirectional"))
      (node (ref "U3") (pin "35") (pinfunction "2A2_35") (pintype "output"))
      (node (ref "U4") (pin "13") (pinfunction "I/O4_13") (pintype "bidirectional"))
    )
    (net (code "63") (name "D_LV7") (class "Default")
      (node (ref "IC2") (pin "15") (pinfunction "PB01_16_15") (pintype "bidirectional"))
      (node (ref "U3") (pin "36") (pinfunction "2A1_36") (pintype "output"))
      (node (ref "U4") (pin "32") (pinfunction "I/O11_32") (pintype "bidirectional"))
    )
    (net (code "64") (name "D_LV8") (class "Default")
      (node (ref "IC2") (pin "135") (pinfunction "PB03_09_135") (pintype "bidirectional"))
      (node (ref "U3") (pin "37") (pinfunction "1A8_37") (pintype "output"))
      (node (ref "U4") (pin "10") (pinfunction "I/O3_10") (pintype "bidirectional"))
    )
    (net (code "65") (name "D_LV9") (class "Default")
      (node (ref "IC2") (pin "136") (pinfunction "PB03_13_136") (pintype "bidirectional"))
      (node (ref "U3") (pin "40") (pinfunction "1A6_40") (pintype "output"))
      (node (ref "U4") (pin "9") (pinfunction "I/O2_9") (pintype "bidirectional"))
    )
    (net (code "66") (name "D_LV10") (class "Default")
      (node (ref "IC2") (pin "13") (pinfunction "PB01_14_13") (pintype "bidirectional"))
      (node (ref "U3") (pin "41") (pinfunction "1A5_41") (pintype "output"))
      (node (ref "U4") (pin "36") (pinfunction "I/O13_36") (pintype "bidirectional"))
    )
    (net (code "67") (name "D_LV11") (class "Default")
      (node (ref "IC2") (pin "11") (pinfunction "PB01_13_11") (pintype "bidirectional"))
      (node (ref "U3") (pin "47") (pinfunction "1A1_47") (pintype "output"))
      (node (ref "U4") (pin "38") (pinfunction "I/O15_38") (pintype "bidirectional"))
    )
    (net (code "68") (name "D_LV12") (class "Default")
      (node (ref "IC2") (pin "138") (pinfunction "PB03_14_138") (pintype "bidirectional"))
      (node (ref "U3") (pin "46") (pinfunction "1A2_46") (pintype "output"))
      (node (ref "U4") (pin "7") (pinfunction "I/O0_7") (pintype "bidirectional"))
    )
    (net (code "69") (name "D_LV13") (class "Default")
      (node (ref "IC2") (pin "12") (pinfunction "PB01_12_12") (pintype "bidirectional"))
      (node (ref "U3") (pin "44") (pinfunction "1A3_44") (pintype "output"))
      (node (ref "U4") (pin "37") (pinfunction "I/O14_37") (pintype "bidirectional"))
    )
    (net (code "70") (name "D_LV14") (class "Default")
      (node (ref "IC2") (pin "137") (pinfunction "PB03_12_137") (pintype "bidirectional"))
      (node (ref "U3") (pin "43") (pinfunction "1A4_43") (pintype "output"))
      (node (ref "U4") (pin "8") (pinfunction "I/O1_8") (pintype "bidirectional"))
    )
    (net (code "71") (name "D_LV15") (class "Default")
      (node (ref "IC2") (pin "14") (pinfunction "PB01_15_14") (pintype "bidirectional"))
      (node (ref "U3") (pin "38") (pinfunction "1A7_38") (pintype "output"))
      (node (ref "U4") (pin "35") (pinfunction "I/O12_35") (pintype "bidirectional"))
    )
    (net (code "72") (name "FTDI_D0") (class "Default")
      (node (ref "IC2") (pin "105") (pinfunction "PB07_16_105") (pintype "bidirectional"))
      (node (ref "U5") (pin "24") (pinfunction "D0_24") (pintype "bidirectional"))
    )
    (net (code "73") (name "FTDI_D1") (class "Default")
      (node (ref "IC2") (pin "102") (pinfunction "PB07_13_102") (pintype "bidirectional"))
      (node (ref "U5") (pin "4") (pinfunction "D1_4") (pintype "bidirectional"))
    )
    (net (code "74") (name "FTDI_D2") (class "Default")
      (node (ref "IC2") (pin "103") (pinfunction "PB07_12_103") (pintype "bidirectional"))
      (node (ref "U5") (pin "2") (pinfunction "D2_2") (pintype "bidirectional"))
    )
    (net (code "75") (name "FTDI_D3") (class "Default")
      (node (ref "IC2") (pin "97") (pinfunction "PB07_03_97") (pintype "bidirectional"))
      (node (ref "U5") (pin "9") (pinfunction "D3_9") (pintype "bidirectional"))
    )
    (net (code "76") (name "FTDI_D4") (class "Default")
      (node (ref "IC2") (pin "104") (pinfunction "PB07_14_104") (pintype "bidirectional"))
      (node (ref "U5") (pin "1") (pinfunction "D4_1") (pintype "bidirectional"))
    )
    (net (code "77") (name "FTDI_D5") (class "Default")
      (node (ref "IC2") (pin "100") (pinfunction "PB07_11_100") (pintype "bidirectional"))
      (node (ref "U5") (pin "7") (pinfunction "D5_7") (pintype "bidirectional"))
    )
    (net (code "78") (name "FTDI_D6") (class "Default")
      (node (ref "IC2") (pin "98") (pinfunction "PB07_10_98") (pintype "bidirectional"))
      (node (ref "U5") (pin "8") (pinfunction "D6_8") (pintype "bidirectional"))
    )
    (net (code "79") (name "FTDI_D7") (class "Default")
      (node (ref "IC2") (pin "101") (pinfunction "PB07_09_101") (pintype "bidirectional"))
      (node (ref "U5") (pin "5") (pinfunction "D7_5") (pintype "bidirectional"))
    )
    (net (code "80") (name "FTDI_RD") (class "Default")
      (node (ref "IC2") (pin "96") (pinfunction "PB07_08_96") (pintype "bidirectional"))
      (node (ref "U5") (pin "11") (pinfunction "~{RD}_11") (pintype "bidirectional"))
    )
    (net (code "81") (name "FTDI_RXF") (class "Default")
      (node (ref "IC2") (pin "106") (pinfunction "PB05_01_106") (pintype "bidirectional"))
      (node (ref "U5") (pin "21") (pinfunction "~{RXF}_21") (pintype "bidirectional"))
    )
    (net (code "82") (name "FTDI_TXE") (class "Default")
      (node (ref "IC2") (pin "107") (pinfunction "PB07_15_107") (pintype "bidirectional"))
      (node (ref "U5") (pin "20") (pinfunction "~{TXE}_20") (pintype "bidirectional"))
    )
    (net (code "83") (name "FTDI_WR") (class "Default")
      (node (ref "IC2") (pin "95") (pinfunction "PB07_02_95") (pintype "bidirectional"))
      (node (ref "U5") (pin "12") (pinfunction "WR_12") (pintype "bidirectional"))
    )
    (net (code "84") (name "GND") (class "Default")
      (node (ref "C1") (pin "2") (pinfunction "2_2") (pintype "passive"))
      (node (ref "C10") (pin "2") (pinfunction "2_2") (pintype "passive"))
      (node (ref "C11") (pin "2") (pinfunction "2_2") (pintype "passive"))
      (node (ref "C12") (pin "2") (pinfunction "2_2") (pintype "passive"))
      (node (ref "C13") (pin "2") (pinfunction "2_2") (pintype "passive"))
      (node (ref "C14") (pin "2") (pinfunction "2_2") (pintype "passive"))
      (node (ref "C15") (pin "2") (pinfunction "2_2") (pintype "passive"))
      (node (ref "C16") (pin "2") (pinfunction "2_2") (pintype "passive"))
      (node (ref "C17") (pin "2") (pinfunction "2_2") (pintype "passive"))
      (node (ref "C18") (pin "2") (pinfunction "2_2") (pintype "passive"))
      (node (ref "C19") (pin "2") (pinfunction "2_2") (pintype "passive"))
      (node (ref "C2") (pin "2") (pinfunction "2_2") (pintype "passive"))
      (node (ref "C20") (pin "2") (pinfunction "2_2") (pintype "passive"))
      (node (ref "C3") (pin "2") (pinfunction "2_2") (pintype "passive"))
      (node (ref "C4") (pin "2") (pinfunction "2_2") (pintype "passive"))
      (node (ref "C5") (pin "2") (pinfunction "2_2") (pintype "passive"))
      (node (ref "C6") (pin "2") (pinfunction "2_2") (pintype "passive"))
      (node (ref "C7") (pin "2") (pinfunction "2_2") (pintype "passive"))
      (node (ref "C8") (pin "2") (pinfunction "2_2") (pintype "passive"))
      (node (ref "C9") (pin "2") (pinfunction "2_2") (pintype "passive"))
      (node (ref "IC1") (pin "1") (pinfunction "ADJ_1") (pintype "input"))
      (node (ref "IC2") (pin "108") (pinfunction "VSSIO_7_108") (pintype "passive"))
      (node (ref "IC2") (pin "114") (pinfunction "VSSINT_4_114") (pintype "passive"))
      (node (ref "IC2") (pin "123") (pinfunction "VSSIO_8_123") (pintype "passive"))
      (node (ref "IC2") (pin "144") (pinfunction "VSSIO_9_144") (pintype "passive"))
      (node (ref "IC2") (pin "18") (pinfunction "VSSIO_1_18") (pintype "passive"))
      (node (ref "IC2") (pin "29") (pinfunction "VSSINT_1_29") (pintype "passive"))
      (node (ref "IC2") (pin "36") (pinfunction "VSSIO_2_36") (pintype "passive"))
      (node (ref "IC2") (pin "47") (pinfunction "VSSIO_3_47") (pintype "passive"))
      (node (ref "IC2") (pin "62") (pinfunction "VSSINT_2_62") (pintype "passive"))
      (node (ref "IC2") (pin "72") (pinfunction "VSSIO_4_72") (pintype "passive"))
      (node (ref "IC2") (pin "89") (pinfunction "VSSIO_5_89") (pintype "passive"))
      (node (ref "IC2") (pin "90") (pinfunction "VSSINT_3_90") (pintype "passive"))
      (node (ref "IC2") (pin "99") (pinfunction "VSSIO_6_99") (pintype "passive"))
      (node (ref "Q1") (pin "2") (pinfunction "E_2") (pintype "passive"))
      (node (ref "Q2") (pin "2") (pinfunction "E_2") (pintype "passive"))
      (node (ref "Q3") (pin "2") (pinfunction "E_2") (pintype "passive"))
      (node (ref "U1") (pin "1") (pinfunction "1DIR_1") (pintype "input"))
      (node (ref "U1") (pin "10") (pinfunction "GND_4_10") (pintype "passive"))
      (node (ref "U1") (pin "15") (pinfunction "GND_15") (pintype "passive"))
      (node (ref "U1") (pin "21") (pinfunction "GND_3_21") (pintype "passive"))
      (node (ref "U1") (pin "24") (pinfunction "2DIR_24") (pintype "input"))
      (node (ref "U1") (pin "25") (pinfunction "2~{OE}_25") (pintype "input"))
      (node (ref "U1") (pin "28") (pinfunction "GND_2_28") (pintype "passive"))
      (node (ref "U1") (pin "34") (pinfunction "GND_3_34") (pintype "passive"))
      (node (ref "U1") (pin "39") (pinfunction "GND_4_39") (pintype "passive"))
      (node (ref "U1") (pin "4") (pinfunction "GND_2_4") (pintype "passive"))
      (node (ref "U1") (pin "45") (pinfunction "GND_45") (pintype "passive"))
      (node (ref "U1") (pin "48") (pinfunction "1~{OE}_48") (pintype "input"))
      (node (ref "U2") (pin "1") (pinfunction "1DIR_1") (pintype "input"))
      (node (ref "U2") (pin "10") (pinfunction "GND_4_10") (pintype "passive"))
      (node (ref "U2") (pin "11") (pinfunction "1B7_11") (pintype "output"))
      (node (ref "U2") (pin "12") (pinfunction "1B8_12") (pintype "output"))
      (node (ref "U2") (pin "13") (pinfunction "2B1_13") (pintype "output"))
      (node (ref "U2") (pin "15") (pinfunction "GND_15") (pintype "passive"))
      (node (ref "U2") (pin "2") (pinfunction "1B1_2") (pintype "output"))
      (node (ref "U2") (pin "21") (pinfunction "GND_3_21") (pintype "passive"))
      (node (ref "U2") (pin "24") (pinfunction "2DIR_24") (pintype "input"))
      (node (ref "U2") (pin "25") (pinfunction "2~{OE}_25") (pintype "input"))
      (node (ref "U2") (pin "28") (pinfunction "GND_2_28") (pintype "passive"))
      (node (ref "U2") (pin "3") (pinfunction "1B2_3") (pintype "output"))
      (node (ref "U2") (pin "34") (pinfunction "GND_3_34") (pintype "passive"))
      (node (ref "U2") (pin "39") (pinfunction "GND_4_39") (pintype "passive"))
      (node (ref "U2") (pin "4") (pinfunction "GND_2_4") (pintype "passive"))
      (node (ref "U2") (pin "45") (pinfunction "GND_45") (pintype "passive"))
      (node (ref "U2") (pin "48") (pinfunction "1~{OE}_48") (pintype "input"))
      (node (ref "U2") (pin "5") (pinfunction "1B3_5") (pintype "output"))
      (node (ref "U2") (pin "6") (pinfunction "1B4_6") (pintype "output"))
      (node (ref "U2") (pin "8") (pinfunction "1B5_8") (pintype "output"))
      (node (ref "U2") (pin "9") (pinfunction "1B6_9") (pintype "output"))
      (node (ref "U3") (pin "10") (pinfunction "GND_4_10") (pintype "passive"))
      (node (ref "U3") (pin "15") (pinfunction "GND_15") (pintype "passive"))
      (node (ref "U3") (pin "21") (pinfunction "GND_3_21") (pintype "passive"))
      (node (ref "U3") (pin "28") (pinfunction "GND_2_28") (pintype "passive"))
      (node (ref "U3") (pin "34") (pinfunction "GND_3_34") (pintype "passive"))
      (node (ref "U3") (pin "39") (pinfunction "GND_4_39") (pintype "passive"))
      (node (ref "U3") (pin "4") (pinfunction "GND_2_4") (pintype "passive"))
      (node (ref "U3") (pin "45") (pinfunction "GND_45") (pintype "passive"))
      (node (ref "U4") (pin "12") (pinfunction "GND_2_12") (pintype "passive"))
      (node (ref "U4") (pin "34") (pinfunction "GND_34") (pintype "passive"))
      (node (ref "U5") (pin "19") (pinfunction "GND_19") (pintype "bidirectional"))
      (node (ref "U5") (pin "6") (pinfunction "GND_6") (pintype "bidirectional"))
      (node (ref "X1") (pin "A16") (pinfunction "S_A16") (pintype "passive"))
      (node (ref "X1") (pin "B16") (pinfunction "S_B16") (pintype "passive"))
      (node (ref "X2") (pin "4") (pinfunction "4_4") (pintype "passive"))
      (node (ref "X3") (pin "6") (pinfunction "S_6") (pintype "passive"))
    )
    (net (code "85") (name "JTCK") (class "Default")
      (node (ref "IC2") (pin "67") (pinfunction "TCK_67") (pintype "input"))
      (node (ref "X3") (pin "3") (pinfunction "S_3") (pintype "passive"))
    )
    (net (code "86") (name "JTDI") (class "Default")
      (node (ref "IC2") (pin "63") (pinfunction "TDI_63") (pintype "input"))
      (node (ref "X3") (pin "1") (pinfunction "S_1") (pintype "passive"))
    )
    (net (code "87") (name "JTDO") (class "Default")
      (node (ref "IC2") (pin "122") (pinfunction "TDO_122") (pintype "output"))
      (node (ref "X3") (pin "4") (pinfunction "S_4") (pintype "passive"))
    )
    (net (code "88") (name "JTMS") (class "Default")
      (node (ref "IC2") (pin "65") (pinfunction "TMS_65") (pintype "input"))
      (node (ref "X3") (pin "2") (pinfunction "S_2") (pintype "passive"))
    )
    (net (code "89") (name "Net-(C6-Pad1)") (class "Default")
      (node (ref "C6") (pin "1") (pinfunction "1_1") (pintype "passive"))
      (node (ref "R1") (pin "1") (pinfunction "1_1") (pintype "passive"))
      (node (ref "X2") (pin "2") (pinfunction "2_2") (pintype "passive"))
    )
    (net (code "90") (name "Net-(C7-Pad1)") (class "Default")
      (node (ref "C7") (pin "1") (pinfunction "1_1") (pintype "passive"))
      (node (ref "R2") (pin "1") (pinfunction "1_1") (pintype "passive"))
      (node (ref "X2") (pin "3") (pinfunction "3_3") (pintype "passive"))
    )
    (net (code "91") (name "Net-(IC2-PB06_08)") (class "Default")
      (node (ref "IC2") (pin "80") (pinfunction "PB06_08_80") (pintype "bidirectional"))
      (node (ref "R8") (pin "1") (pinfunction "1_1") (pintype "passive"))
    )
    (net (code "92") (name "Net-(IC2-PB06_10)") (class "Default")
      (node (ref "IC2") (pin "82") (pinfunction "PB06_10_82") (pintype "bidirectional"))
      (node (ref "R6") (pin "1") (pinfunction "1_1") (pintype "passive"))
    )
    (net (code "93") (name "Net-(IC2-PB06_12)") (class "Default")
      (node (ref "IC2") (pin "81") (pinfunction "PB06_12_81") (pintype "bidirectional"))
      (node (ref "R7") (pin "1") (pinfunction "1_1") (pintype "passive"))
    )
    (net (code "94") (name "Net-(L1-Pad1)") (class "Default")
      (node (ref "L1") (pin "1") (pinfunction "1_1") (pintype "passive"))
      (node (ref "X2") (pin "1") (pinfunction "1_1") (pintype "passive"))
    )
    (net (code "95") (name "Net-(LED1-PadC)") (class "Default")
      (node (ref "LED1") (pin "C") (pinfunction "C_C") (pintype "passive"))
      (node (ref "R3") (pin "2") (pinfunction "2_2") (pintype "passive"))
    )
    (net (code "96") (name "Net-(LED2-PadC)") (class "Default")
      (node (ref "LED2") (pin "C") (pinfunction "C_C") (pintype "passive"))
      (node (ref "R4") (pin "2") (pinfunction "2_2") (pintype "passive"))
    )
    (net (code "97") (name "Net-(LED3-PadC)") (class "Default")
      (node (ref "LED3") (pin "C") (pinfunction "C_C") (pintype "passive"))
      (node (ref "R5") (pin "2") (pinfunction "2_2") (pintype "passive"))
    )
    (net (code "98") (name "Net-(Q1-B)") (class "Default")
      (node (ref "Q1") (pin "1") (pinfunction "B_1") (pintype "passive"))
      (node (ref "R6") (pin "2") (pinfunction "2_2") (pintype "passive"))
    )
    (net (code "99") (name "Net-(Q1-C)") (class "Default")
      (node (ref "Q1") (pin "3") (pinfunction "C_3") (pintype "passive"))
      (node (ref "R3") (pin "1") (pinfunction "1_1") (pintype "passive"))
    )
    (net (code "100") (name "Net-(Q2-B)") (class "Default")
      (node (ref "Q2") (pin "1") (pinfunction "B_1") (pintype "passive"))
      (node (ref "R7") (pin "2") (pinfunction "2_2") (pintype "passive"))
    )
    (net (code "101") (name "Net-(Q2-C)") (class "Default")
      (node (ref "Q2") (pin "3") (pinfunction "C_3") (pintype "passive"))
      (node (ref "R4") (pin "1") (pinfunction "1_1") (pintype "passive"))
    )
    (net (code "102") (name "Net-(Q3-B)") (class "Default")
      (node (ref "Q3") (pin "1") (pinfunction "B_1") (pintype "passive"))
      (node (ref "R8") (pin "2") (pinfunction "2_2") (pintype "passive"))
    )
    (net (code "103") (name "Net-(Q3-C)") (class "Default")
      (node (ref "Q3") (pin "3") (pinfunction "C_3") (pintype "passive"))
      (node (ref "R5") (pin "1") (pinfunction "1_1") (pintype "passive"))
    )
    (net (code "104") (name "Net-(U5-3V3OUT)") (class "Default")
      (node (ref "C8") (pin "1") (pinfunction "1_1") (pintype "passive"))
      (node (ref "C9") (pin "1") (pinfunction "1_1") (pintype "passive"))
      (node (ref "U5") (pin "15") (pinfunction "3V3OUT_15") (pintype "bidirectional"))
      (node (ref "U5") (pin "16") (pinfunction "~{RESET}_16") (pintype "bidirectional"))
      (node (ref "U5") (pin "3") (pinfunction "VCCIO_3") (pintype "bidirectional"))
    )
    (net (code "105") (name "Net-(U5-USBDM)") (class "Default")
      (node (ref "R1") (pin "2") (pinfunction "2_2") (pintype "passive"))
      (node (ref "U5") (pin "14") (pinfunction "USBDM_14") (pintype "bidirectional"))
    )
    (net (code "106") (name "Net-(U5-USBDP)") (class "Default")
      (node (ref "R2") (pin "2") (pinfunction "2_2") (pintype "passive"))
      (node (ref "U5") (pin "13") (pinfunction "USBDP_13") (pintype "bidirectional"))
    )
    (net (code "107") (name "Net-(U5-VCC)") (class "Default")
      (node (ref "L1") (pin "2") (pinfunction "2_2") (pintype "passive"))
      (node (ref "U5") (pin "18") (pinfunction "VCC_18") (pintype "bidirectional"))
    )
    (net (code "108") (name "RAMA0") (class "Default")
      (node (ref "IC2") (pin "140") (pinfunction "PB03_16_140") (pintype "bidirectional"))
      (node (ref "U4") (pin "5") (pinfunction "A0_5") (pintype "input"))
    )
    (net (code "109") (name "RAMA1") (class "Default")
      (node (ref "IC2") (pin "142") (pinfunction "PB01_00_142") (pintype "bidirectional"))
      (node (ref "U4") (pin "4") (pinfunction "A1_4") (pintype "input"))
    )
    (net (code "110") (name "RAMA2") (class "Default")
      (node (ref "IC2") (pin "143") (pinfunction "PB01_01_143") (pintype "bidirectional"))
      (node (ref "U4") (pin "3") (pinfunction "A2_3") (pintype "input"))
    )
    (net (code "111") (name "RAMA3") (class "Default")
      (node (ref "IC2") (pin "2") (pinfunction "PB01_04_2") (pintype "bidirectional"))
      (node (ref "U4") (pin "2") (pinfunction "A3_2") (pintype "input"))
    )
    (net (code "112") (name "RAMA4") (class "Default")
      (node (ref "IC2") (pin "3") (pinfunction "PB01_05_3") (pintype "bidirectional"))
      (node (ref "U4") (pin "1") (pinfunction "A4_1") (pintype "input"))
    )
    (net (code "113") (name "RAMA5") (class "Default")
      (node (ref "IC2") (pin "4") (pinfunction "PB01_03_4") (pintype "bidirectional"))
      (node (ref "U4") (pin "44") (pinfunction "A5_44") (pintype "input"))
    )
    (net (code "114") (name "RAMA6") (class "Default")
      (node (ref "IC2") (pin "5") (pinfunction "PB01_07_5") (pintype "bidirectional"))
      (node (ref "U4") (pin "43") (pinfunction "A6_43") (pintype "input"))
    )
    (net (code "115") (name "RAMA7") (class "Default")
      (node (ref "IC2") (pin "6") (pinfunction "PB01_08_6") (pintype "bidirectional"))
      (node (ref "U4") (pin "42") (pinfunction "A7_42") (pintype "input"))
    )
    (net (code "116") (name "RAMA8") (class "Default")
      (node (ref "IC2") (pin "20") (pinfunction "PB00_05_20") (pintype "bidirectional"))
      (node (ref "U4") (pin "27") (pinfunction "A8_27") (pintype "input"))
    )
    (net (code "117") (name "RAMA9") (class "Default")
      (node (ref "IC2") (pin "21") (pinfunction "PB00_07_21") (pintype "bidirectional"))
      (node (ref "U4") (pin "26") (pinfunction "A9_26") (pintype "input"))
    )
    (net (code "118") (name "RAMA10") (class "Default")
      (node (ref "IC2") (pin "22") (pinfunction "PB00_08_22") (pintype "bidirectional"))
      (node (ref "U4") (pin "25") (pinfunction "A10_25") (pintype "input"))
    )
    (net (code "119") (name "RAMA11") (class "Default")
      (node (ref "IC2") (pin "23") (pinfunction "PB00_00_23") (pintype "bidirectional"))
      (node (ref "U4") (pin "24") (pinfunction "A11_24") (pintype "input"))
    )
    (net (code "120") (name "RAMA12") (class "Default")
      (node (ref "IC2") (pin "25") (pinfunction "PB00_03_25") (pintype "bidirectional"))
      (node (ref "U4") (pin "22") (pinfunction "A12_22") (pintype "input"))
    )
    (net (code "121") (name "RAMA13") (class "Default")
      (node (ref "IC2") (pin "26") (pinfunction "PB00_11_26") (pintype "bidirectional"))
      (node (ref "U4") (pin "21") (pinfunction "A13_21") (pintype "input"))
    )
    (net (code "122") (name "RAMA14") (class "Default")
      (node (ref "IC2") (pin "27") (pinfunction "PB00_13_27") (pintype "bidirectional"))
      (node (ref "U4") (pin "20") (pinfunction "A14_20") (pintype "input"))
    )
    (net (code "123") (name "RAMA15") (class "Default")
      (node (ref "IC2") (pin "28") (pinfunction "PB00_14_28") (pintype "bidirectional"))
      (node (ref "U4") (pin "19") (pinfunction "A15_19") (pintype "input"))
    )
    (net (code "124") (name "RAMA16") (class "Default")
      (node (ref "IC2") (pin "30") (pinfunction "PB00_16_30") (pintype "bidirectional"))
      (node (ref "U4") (pin "18") (pinfunction "A16_18") (pintype "input"))
    )
    (net (code "125") (name "RAMA17") (class "Default")
      (node (ref "IC2") (pin "24") (pinfunction "PB00_10_24") (pintype "bidirectional"))
      (node (ref "U4") (pin "23") (pinfunction "A17_23") (pintype "input"))
    )
    (net (code "126") (name "TGT_DIR") (class "Default")
      (node (ref "IC2") (pin "41") (pinfunction "PB02_02_41") (pintype "bidirectional"))
      (node (ref "U3") (pin "1") (pinfunction "1DIR_1") (pintype "input"))
      (node (ref "U3") (pin "24") (pinfunction "2DIR_24") (pintype "input"))
    )
    (net (code "127") (name "unconnected-(IC2-PB02_00-Pad39)") (class "Default")
      (node (ref "IC2") (pin "39") (pinfunction "PB02_00_39") (pintype "bidirectional"))
    )
    (net (code "128") (name "unconnected-(IC2-PB03_00-Pad118)") (class "Default")
      (node (ref "IC2") (pin "118") (pinfunction "PB03_00_118") (pintype "bidirectional"))
    )
    (net (code "129") (name "unconnected-(IC2-PB03_01-Pad126)") (class "Default")
      (node (ref "IC2") (pin "126") (pinfunction "PB03_01_126") (pintype "bidirectional"))
    )
    (net (code "130") (name "unconnected-(IC2-PB03_02-Pad133)") (class "Default")
      (node (ref "IC2") (pin "133") (pinfunction "PB03_02_133") (pintype "bidirectional"))
    )
    (net (code "131") (name "unconnected-(IC2-PB03_04-Pad128)") (class "Default")
      (node (ref "IC2") (pin "128") (pinfunction "PB03_04_128") (pintype "bidirectional"))
    )
    (net (code "132") (name "unconnected-(IC2-PB03_05-Pad129)") (class "Default")
      (node (ref "IC2") (pin "129") (pinfunction "PB03_05_129") (pintype "bidirectional"))
    )
    (net (code "133") (name "unconnected-(IC2-PB03_07-Pad130)") (class "Default")
      (node (ref "IC2") (pin "130") (pinfunction "PB03_07_130") (pintype "bidirectional"))
    )
    (net (code "134") (name "unconnected-(IC2-PB03_08-Pad131)") (class "Default")
      (node (ref "IC2") (pin "131") (pinfunction "PB03_08_131") (pintype "bidirectional"))
    )
    (net (code "135") (name "unconnected-(IC2-PB03_10-Pad132)") (class "Default")
      (node (ref "IC2") (pin "132") (pinfunction "PB03_10_132") (pintype "bidirectional"))
    )
    (net (code "136") (name "unconnected-(IC2-PB03_11-Pad134)") (class "Default")
      (node (ref "IC2") (pin "134") (pinfunction "PB03_11_134") (pintype "bidirectional"))
    )
    (net (code "137") (name "unconnected-(IC2-PB05_03-Pad111)") (class "Default")
      (node (ref "IC2") (pin "111") (pinfunction "PB05_03_111") (pintype "bidirectional"))
    )
    (net (code "138") (name "unconnected-(IC2-PB05_04-Pad110)") (class "Default")
      (node (ref "IC2") (pin "110") (pinfunction "PB05_04_110") (pintype "bidirectional"))
    )
    (net (code "139") (name "unconnected-(IC2-PB05_05-Pad112)") (class "Default")
      (node (ref "IC2") (pin "112") (pinfunction "PB05_05_112") (pintype "bidirectional"))
    )
    (net (code "140") (name "unconnected-(IC2-PB05_07-Pad113)") (class "Default")
      (node (ref "IC2") (pin "113") (pinfunction "PB05_07_113") (pintype "bidirectional"))
    )
    (net (code "141") (name "unconnected-(IC2-PB05_08-Pad116)") (class "Default")
      (node (ref "IC2") (pin "116") (pinfunction "PB05_08_116") (pintype "bidirectional"))
    )
    (net (code "142") (name "unconnected-(IC2-PB05_09-Pad115)") (class "Default")
      (node (ref "IC2") (pin "115") (pinfunction "PB05_09_115") (pintype "bidirectional"))
    )
    (net (code "143") (name "unconnected-(IC2-PB05_10-Pad119)") (class "Default")
      (node (ref "IC2") (pin "119") (pinfunction "PB05_10_119") (pintype "bidirectional"))
    )
    (net (code "144") (name "unconnected-(IC2-PB05_11-Pad120)") (class "Default")
      (node (ref "IC2") (pin "120") (pinfunction "PB05_11_120") (pintype "bidirectional"))
    )
    (net (code "145") (name "unconnected-(IC2-PB05_13-Pad121)") (class "Default")
      (node (ref "IC2") (pin "121") (pinfunction "PB05_13_121") (pintype "bidirectional"))
    )
    (net (code "146") (name "unconnected-(IC2-PB05_14-Pad124)") (class "Default")
      (node (ref "IC2") (pin "124") (pinfunction "PB05_14_124") (pintype "bidirectional"))
    )
    (net (code "147") (name "unconnected-(IC2-PB05_15-Pad117)") (class "Default")
      (node (ref "IC2") (pin "117") (pinfunction "PB05_15_117") (pintype "bidirectional"))
    )
    (net (code "148") (name "unconnected-(IC2-PB05_16-Pad125)") (class "Default")
      (node (ref "IC2") (pin "125") (pinfunction "PB05_16_125") (pintype "bidirectional"))
    )
    (net (code "149") (name "unconnected-(IC2-PB06_02-Pad75)") (class "Default")
      (node (ref "IC2") (pin "75") (pinfunction "PB06_02_75") (pintype "bidirectional"))
    )
    (net (code "150") (name "unconnected-(IC2-PB06_04-Pad74)") (class "Default")
      (node (ref "IC2") (pin "74") (pinfunction "PB06_04_74") (pintype "bidirectional"))
    )
    (net (code "151") (name "unconnected-(IC2-PB06_05-Pad76)") (class "Default")
      (node (ref "IC2") (pin "76") (pinfunction "PB06_05_76") (pintype "bidirectional"))
    )
    (net (code "152") (name "unconnected-(IC2-PB06_06-Pad77)") (class "Default")
      (node (ref "IC2") (pin "77") (pinfunction "PB06_06_77") (pintype "bidirectional"))
    )
    (net (code "153") (name "unconnected-(IC2-PB06_07-Pad78)") (class "Default")
      (node (ref "IC2") (pin "78") (pinfunction "PB06_07_78") (pintype "bidirectional"))
    )
    (net (code "154") (name "unconnected-(IC2-PB06_09-Pad79)") (class "Default")
      (node (ref "IC2") (pin "79") (pinfunction "PB06_09_79") (pintype "bidirectional"))
    )
    (net (code "155") (name "unconnected-(IC2-PB06_11-Pad85)") (class "Default")
      (node (ref "IC2") (pin "85") (pinfunction "PB06_11_85") (pintype "bidirectional"))
    )
    (net (code "156") (name "unconnected-(IC2-PB06_13-Pad86)") (class "Default")
      (node (ref "IC2") (pin "86") (pinfunction "PB06_13_86") (pintype "bidirectional"))
    )
    (net (code "157") (name "unconnected-(IC2-PB06_14-Pad87)") (class "Default")
      (node (ref "IC2") (pin "87") (pinfunction "PB06_14_87") (pintype "bidirectional"))
    )
    (net (code "158") (name "unconnected-(IC2-PB06_15-Pad83)") (class "Default")
      (node (ref "IC2") (pin "83") (pinfunction "PB06_15_83") (pintype "bidirectional"))
    )
    (net (code "159") (name "unconnected-(IC2-PB06_16-Pad88)") (class "Default")
      (node (ref "IC2") (pin "88") (pinfunction "PB06_16_88") (pintype "bidirectional"))
    )
    (net (code "160") (name "unconnected-(IC2-PB07_01-Pad91)") (class "Default")
      (node (ref "IC2") (pin "91") (pinfunction "PB07_01_91") (pintype "bidirectional"))
    )
    (net (code "161") (name "unconnected-(IC2-PB07_04-Pad92)") (class "Default")
      (node (ref "IC2") (pin "92") (pinfunction "PB07_04_92") (pintype "bidirectional"))
    )
    (net (code "162") (name "unconnected-(IC2-PB07_05-Pad93)") (class "Default")
      (node (ref "IC2") (pin "93") (pinfunction "PB07_05_93") (pintype "bidirectional"))
    )
    (net (code "163") (name "unconnected-(IC2-PB07_07-Pad94)") (class "Default")
      (node (ref "IC2") (pin "94") (pinfunction "PB07_07_94") (pintype "bidirectional"))
    )
    (net (code "164") (name "unconnected-(U2B-1A1-Pad47)") (class "Default")
      (node (ref "U2") (pin "47") (pinfunction "1A1_47") (pintype "output"))
    )
    (net (code "165") (name "unconnected-(U2B-1A2-Pad46)") (class "Default")
      (node (ref "U2") (pin "46") (pinfunction "1A2_46") (pintype "output"))
    )
    (net (code "166") (name "unconnected-(U2B-1A3-Pad44)") (class "Default")
      (node (ref "U2") (pin "44") (pinfunction "1A3_44") (pintype "output"))
    )
    (net (code "167") (name "unconnected-(U2B-1A4-Pad43)") (class "Default")
      (node (ref "U2") (pin "43") (pinfunction "1A4_43") (pintype "output"))
    )
    (net (code "168") (name "unconnected-(U2B-1A5-Pad41)") (class "Default")
      (node (ref "U2") (pin "41") (pinfunction "1A5_41") (pintype "output"))
    )
    (net (code "169") (name "unconnected-(U2B-1A6-Pad40)") (class "Default")
      (node (ref "U2") (pin "40") (pinfunction "1A6_40") (pintype "output"))
    )
    (net (code "170") (name "unconnected-(U2B-1A7-Pad38)") (class "Default")
      (node (ref "U2") (pin "38") (pinfunction "1A7_38") (pintype "output"))
    )
    (net (code "171") (name "unconnected-(U2B-1A8-Pad37)") (class "Default")
      (node (ref "U2") (pin "37") (pinfunction "1A8_37") (pintype "output"))
    )
    (net (code "172") (name "unconnected-(U2B-2A1-Pad36)") (class "Default")
      (node (ref "U2") (pin "36") (pinfunction "2A1_36") (pintype "output"))
    )
    (net (code "173") (name "unconnected-(U4-NC-Pad28)") (class "Default")
      (node (ref "U4") (pin "28") (pinfunction "NC_28") (pintype "no_connect"))
    )
    (net (code "174") (name "unconnected-(U5-CBUS6-Pad22)") (class "Default")
      (node (ref "U5") (pin "22") (pinfunction "CBUS6_22") (pintype "bidirectional"))
    )
    (net (code "175") (name "unconnected-(U5-SIWU-Pad10)") (class "Default")
      (node (ref "U5") (pin "10") (pinfunction "SIWU_10") (pintype "bidirectional"))
    )
    (net (code "176") (name "unconnected-(U5-VCORE-Pad17)") (class "Default")
      (node (ref "U5") (pin "17") (pinfunction "VCORE_17") (pintype "bidirectional"))
    )
    (net (code "177") (name "unconnected-(X1AG-S-PadC1)") (class "Default")
      (node (ref "X1") (pin "C1") (pinfunction "S_C1") (pintype "passive"))
    )
    (net (code "178") (name "unconnected-(X1F-S-PadA14)") (class "Default")
      (node (ref "X1") (pin "A14") (pinfunction "S_A14") (pintype "passive"))
    )
    (net (code "179") (name "unconnected-(X1G-S-PadA15)") (class "Default")
      (node (ref "X1") (pin "A15") (pinfunction "S_A15") (pintype "passive"))
    )
    (net (code "180") (name "unconnected-(X1V-S-PadB14)") (class "Default")
      (node (ref "X1") (pin "B14") (pinfunction "S_B14") (pintype "passive"))
    )
    (net (code "181") (name "unconnected-(X1W-S-PadB15)") (class "Default")
      (node (ref "X1") (pin "B15") (pinfunction "S_B15") (pintype "passive"))
    )
    (net (code "182") (name "unconnected-(X2-PadS1)") (class "Default")
      (node (ref "X2") (pin "S1") (pinfunction "S1_S1") (pintype "passive"))
    )
    (net (code "183") (name "unconnected-(X2-PadS2)") (class "Default")
      (node (ref "X2") (pin "S2") (pinfunction "S2_S2") (pintype "passive"))
    )
    (net (code "184") (name "{slash}CE") (class "Default")
      (node (ref "U2") (pin "14") (pinfunction "2B2_14") (pintype "output"))
      (node (ref "X1") (pin "C11") (pinfunction "S_C11") (pintype "passive"))
    )
    (net (code "185") (name "{slash}CE_LV") (class "Default")
      (node (ref "IC2") (pin "43") (pinfunction "PB02_10_43") (pintype "bidirectional"))
      (node (ref "U2") (pin "35") (pinfunction "2A2_35") (pintype "output"))
    )
    (net (code "186") (name "{slash}OEH") (class "Default")
      (node (ref "U2") (pin "19") (pinfunction "2B5_19") (pintype "output"))
      (node (ref "X1") (pin "C9") (pinfunction "S_C9") (pintype "passive"))
    )
    (net (code "187") (name "{slash}OEH_LV") (class "Default")
      (node (ref "IC2") (pin "46") (pinfunction "PB02_06_46") (pintype "bidirectional"))
      (node (ref "U2") (pin "30") (pinfunction "2A5_30") (pintype "output"))
    )
    (net (code "188") (name "{slash}OEL") (class "Default")
      (node (ref "U2") (pin "17") (pinfunction "2B4_17") (pintype "output"))
      (node (ref "X1") (pin "A10") (pinfunction "S_A10") (pintype "passive"))
    )
    (net (code "189") (name "{slash}OEL_LV") (class "Default")
      (node (ref "IC2") (pin "45") (pinfunction "PB02_11_45") (pintype "bidirectional"))
      (node (ref "U2") (pin "32") (pinfunction "2A4_32") (pintype "output"))
    )
    (net (code "190") (name "{slash}PGMH") (class "Default")
      (node (ref "U1") (pin "20") (pinfunction "2B6_20") (pintype "output"))
      (node (ref "X1") (pin "C2") (pinfunction "S_C2") (pintype "passive"))
    )
    (net (code "191") (name "{slash}PGMH_LV") (class "Default")
      (node (ref "IC2") (pin "69") (pinfunction "PB04_16_69") (pintype "bidirectional"))
      (node (ref "U1") (pin "29") (pinfunction "2A6_29") (pintype "output"))
    )
    (net (code "192") (name "{slash}PGML") (class "Default")
      (node (ref "U1") (pin "23") (pinfunction "2B8_23") (pintype "output"))
      (node (ref "X1") (pin "A2") (pinfunction "S_A2") (pintype "passive"))
    )
    (net (code "193") (name "{slash}PGML_LV") (class "Default")
      (node (ref "IC2") (pin "71") (pinfunction "PB06_01_71") (pintype "bidirectional"))
      (node (ref "U1") (pin "26") (pinfunction "2A8_26") (pintype "output"))
    )
    (net (code "194") (name "{slash}RAM_CS") (class "Default")
      (node (ref "IC2") (pin "139") (pinfunction "PB03_15_139") (pintype "bidirectional"))
      (node (ref "U4") (pin "6") (pinfunction "~{CS1}_6") (pintype "input"))
    )
    (net (code "195") (name "{slash}RAM_LB") (class "Default")
      (node (ref "IC2") (pin "10") (pinfunction "PB01_11_10") (pintype "bidirectional"))
      (node (ref "U4") (pin "39") (pinfunction "~{LB}_39") (pintype "passive"))
    )
    (net (code "196") (name "{slash}RAM_OE") (class "Default")
      (node (ref "IC2") (pin "7") (pinfunction "PB01_09_7") (pintype "bidirectional"))
      (node (ref "U4") (pin "41") (pinfunction "~{OE}_41") (pintype "input"))
    )
    (net (code "197") (name "{slash}RAM_UB") (class "Default")
      (node (ref "IC2") (pin "9") (pinfunction "PB01_10_9") (pintype "bidirectional"))
      (node (ref "U4") (pin "40") (pinfunction "~{UB}_40") (pintype "passive"))
    )
    (net (code "198") (name "{slash}RAM_WE") (class "Default")
      (node (ref "IC2") (pin "31") (pinfunction "PB00_09_31") (pintype "bidirectional"))
      (node (ref "U4") (pin "17") (pinfunction "~{WE}_17") (pintype "input"))
    )
    (net (code "199") (name "{slash}TGT_DEN") (class "Default")
      (node (ref "IC2") (pin "40") (pinfunction "PB02_08_40") (pintype "bidirectional"))
      (node (ref "U3") (pin "25") (pinfunction "2~{OE}_25") (pintype "input"))
      (node (ref "U3") (pin "48") (pinfunction "1~{OE}_48") (pintype "input"))
    )
  )
)
